# galvanika-board-2_2.net
KiCad netlist of a schematic drawn in EAGLE
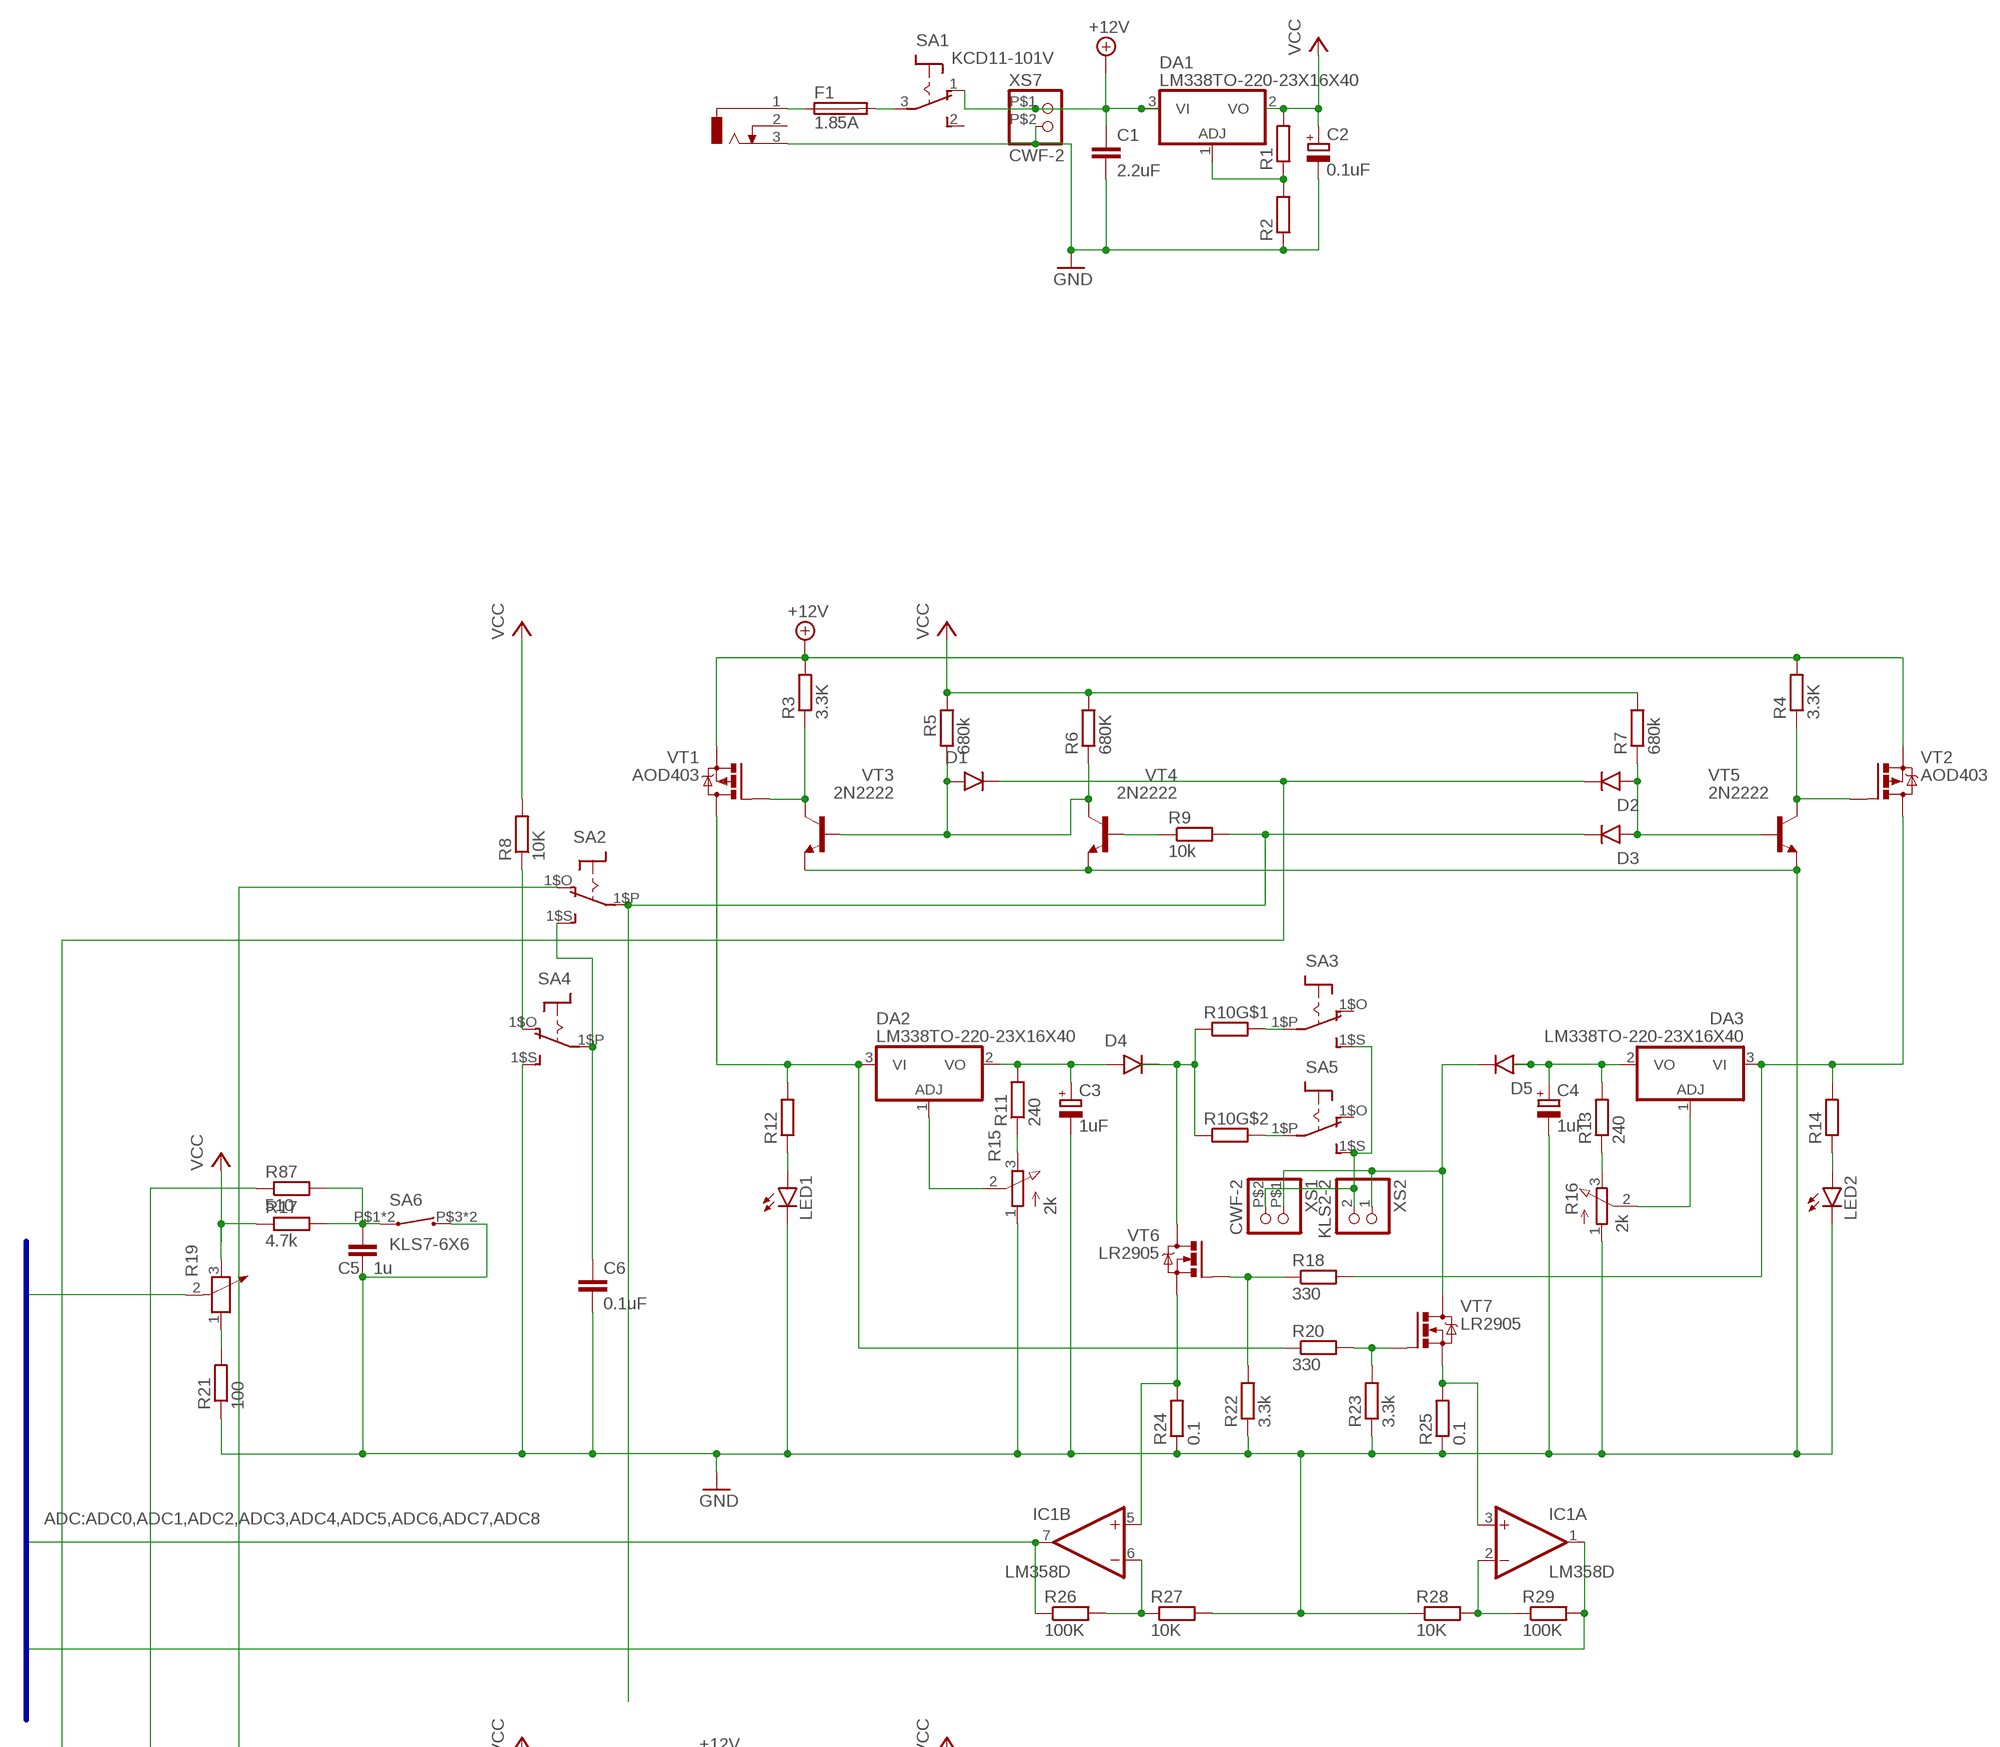
[diagram p0: schematic, sheet 1, part 1 of 2]
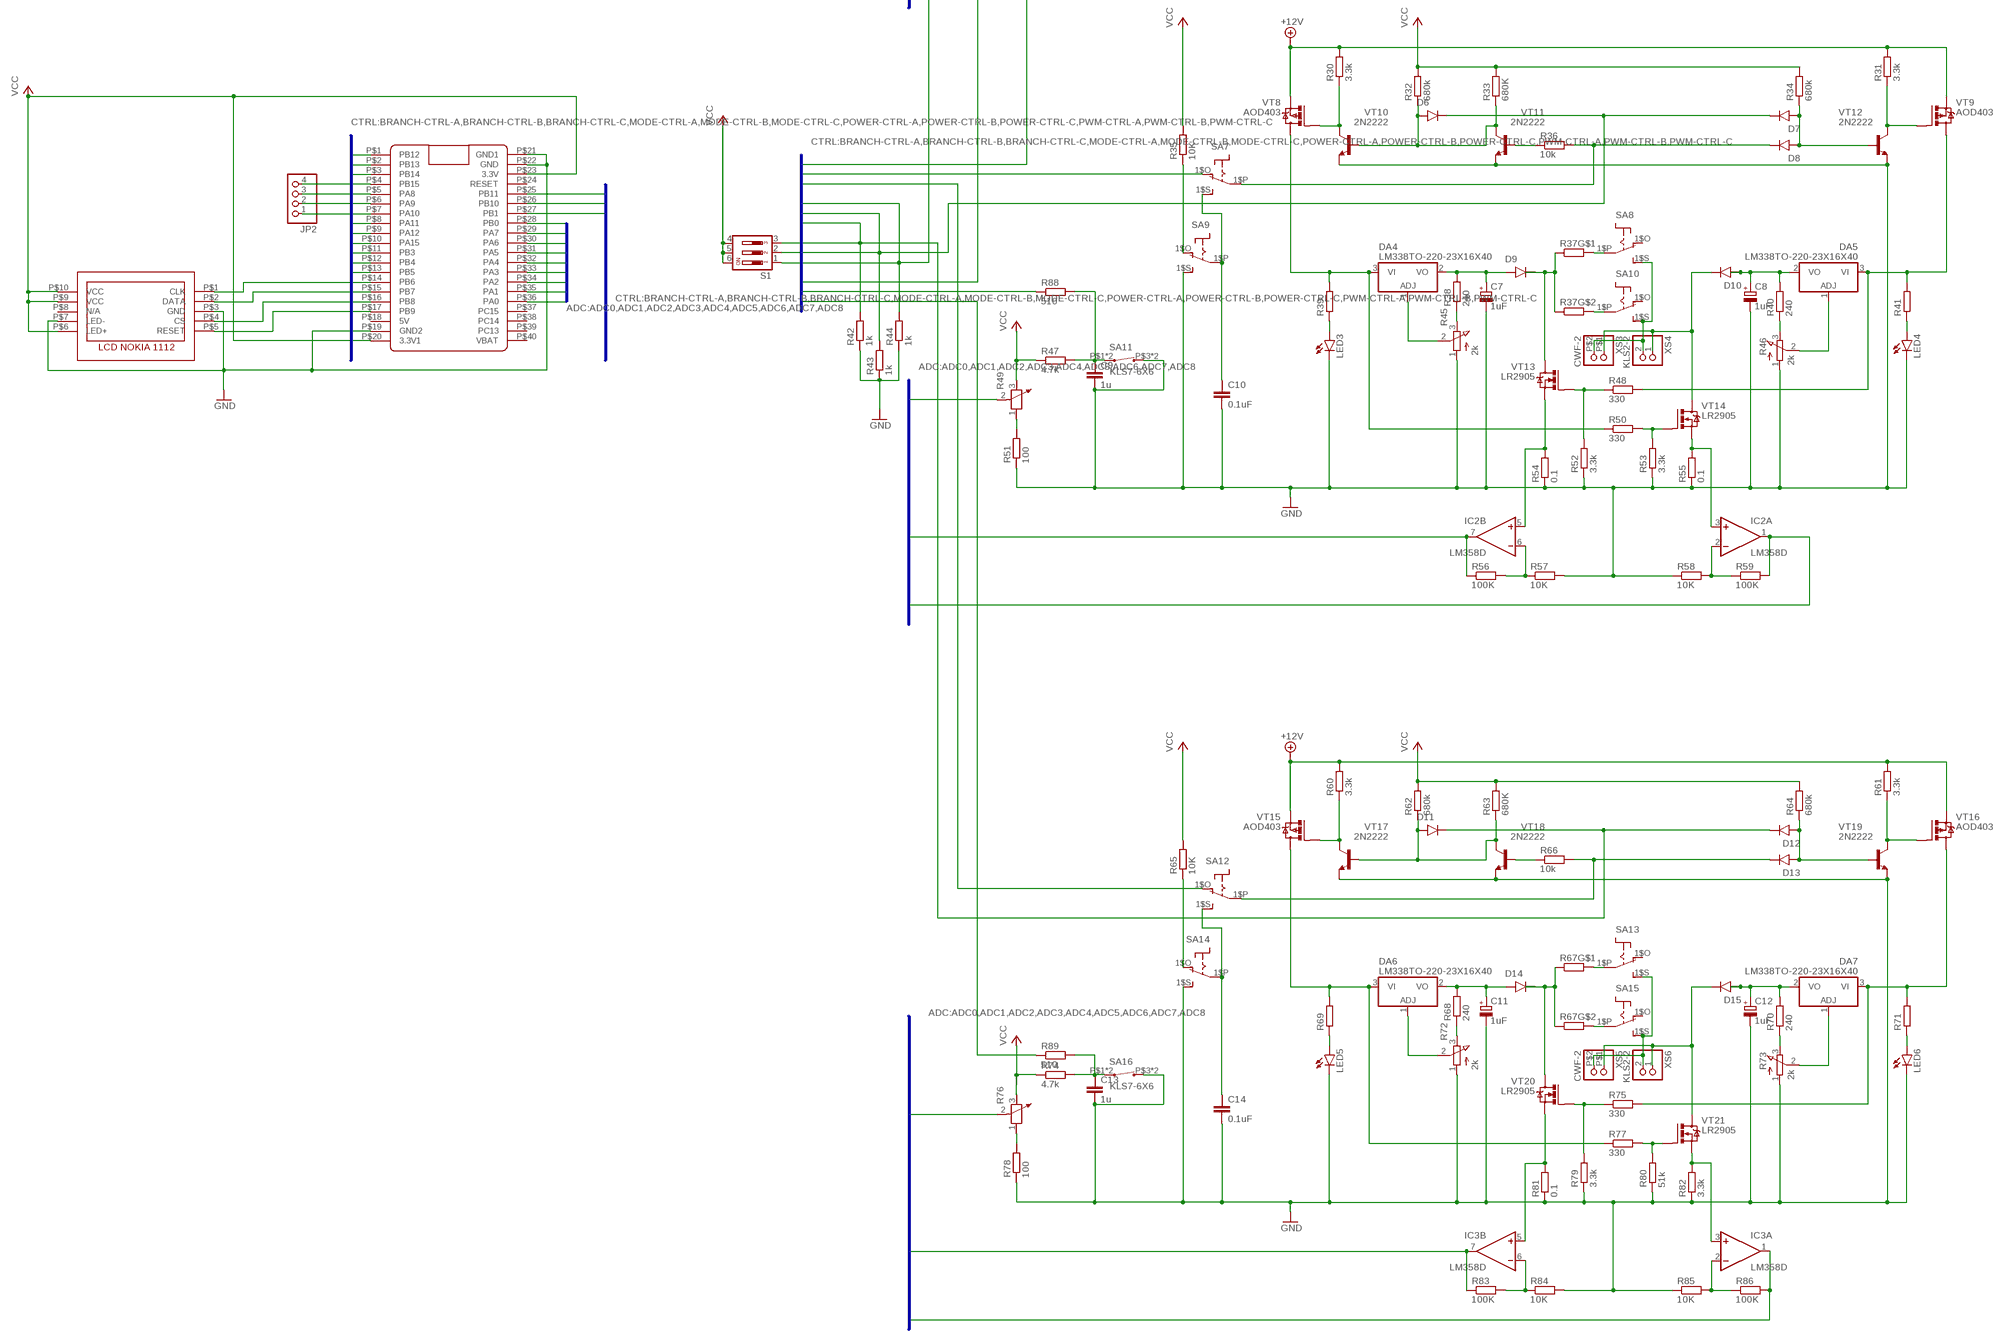
[diagram p1: schematic, sheet 1, part 2 of 2]

(export (version "E")
  (design (tool "Eeschema 10.0.6"))
  (components
    (comp (ref "C1")
      (value "2.2uF")
      (footprint "eagle-import:C025-025X050")
      (libsource (lib "eagle-import") (part "C-EU025-025X050"))
    )
    (comp (ref "C2")
      (value "0.1uF")
      (footprint "eagle-import:E2,5-5")
      (libsource (lib "eagle-import") (part "rcl_334_CPOL-EUE2.5-5"))
    )
    (comp (ref "C3")
      (value "1uF")
      (footprint "eagle-import:E5-4")
      (libsource (lib "eagle-import") (part "CPOL-EUE5-4"))
    )
    (comp (ref "C4")
      (value "1uF")
      (footprint "eagle-import:E5-4")
      (libsource (lib "eagle-import") (part "CPOL-EUE5-4"))
    )
    (comp (ref "C5")
      (value "1u")
      (footprint "eagle-import:C1206")
      (libsource (lib "eagle-import") (part "C-EUC1206"))
    )
    (comp (ref "C6")
      (value "0.1uF")
      (footprint "eagle-import:C1206")
      (libsource (lib "eagle-import") (part "C-EUC1206"))
    )
    (comp (ref "C7")
      (value "1uF")
      (footprint "eagle-import:E5-4")
      (libsource (lib "eagle-import") (part "CPOL-EUE5-4"))
    )
    (comp (ref "C8")
      (value "1uF")
      (footprint "eagle-import:E5-4")
      (libsource (lib "eagle-import") (part "CPOL-EUE5-4"))
    )
    (comp (ref "C9")
      (value "1u")
      (footprint "eagle-import:C1206")
      (libsource (lib "eagle-import") (part "C-EUC1206"))
    )
    (comp (ref "C10")
      (value "0.1uF")
      (footprint "eagle-import:C1206")
      (libsource (lib "eagle-import") (part "C-EUC1206"))
    )
    (comp (ref "C11")
      (value "1uF")
      (footprint "eagle-import:E5-4")
      (libsource (lib "eagle-import") (part "CPOL-EUE5-4"))
    )
    (comp (ref "C12")
      (value "1uF")
      (footprint "eagle-import:E5-4")
      (libsource (lib "eagle-import") (part "CPOL-EUE5-4"))
    )
    (comp (ref "C13")
      (value "1u")
      (footprint "eagle-import:C1206")
      (libsource (lib "eagle-import") (part "C-EUC1206"))
    )
    (comp (ref "C14")
      (value "0.1uF")
      (footprint "eagle-import:C1206")
      (libsource (lib "eagle-import") (part "C-EUC1206"))
    )
    (comp (ref "D1")
      (value "1N4001")
      (footprint "eagle-import:DO41-10")
      (libsource (lib "eagle-import") (part "1N4001"))
    )
    (comp (ref "D2")
      (value "1N4001")
      (footprint "eagle-import:DO41-10")
      (libsource (lib "eagle-import") (part "1N4001"))
    )
    (comp (ref "D3")
      (value "1N4001")
      (footprint "eagle-import:DO41-10")
      (libsource (lib "eagle-import") (part "1N4001"))
    )
    (comp (ref "D4")
      (value "1N4001")
      (footprint "eagle-import:DO41-10")
      (libsource (lib "eagle-import") (part "1N4001"))
    )
    (comp (ref "D5")
      (value "1N4001")
      (footprint "eagle-import:DO41-10")
      (libsource (lib "eagle-import") (part "1N4001"))
    )
    (comp (ref "D6")
      (value "1N4001")
      (footprint "eagle-import:DO41-10")
      (libsource (lib "eagle-import") (part "1N4001"))
    )
    (comp (ref "D7")
      (value "1N4001")
      (footprint "eagle-import:DO41-10")
      (libsource (lib "eagle-import") (part "1N4001"))
    )
    (comp (ref "D8")
      (value "1N4001")
      (footprint "eagle-import:DO41-10")
      (libsource (lib "eagle-import") (part "1N4001"))
    )
    (comp (ref "D9")
      (value "1N4001")
      (footprint "eagle-import:DO41-10")
      (libsource (lib "eagle-import") (part "1N4001"))
    )
    (comp (ref "D10")
      (value "1N4001")
      (footprint "eagle-import:DO41-10")
      (libsource (lib "eagle-import") (part "1N4001"))
    )
    (comp (ref "D11")
      (value "1N4001")
      (footprint "eagle-import:DO41-10")
      (libsource (lib "eagle-import") (part "1N4001"))
    )
    (comp (ref "D12")
      (value "1N4001")
      (footprint "eagle-import:DO41-10")
      (libsource (lib "eagle-import") (part "1N4001"))
    )
    (comp (ref "D13")
      (value "1N4001")
      (footprint "eagle-import:DO41-10")
      (libsource (lib "eagle-import") (part "1N4001"))
    )
    (comp (ref "D14")
      (value "1N4001")
      (footprint "eagle-import:DO41-10")
      (libsource (lib "eagle-import") (part "1N4001"))
    )
    (comp (ref "D15")
      (value "1N4001")
      (footprint "eagle-import:DO41-10")
      (libsource (lib "eagle-import") (part "1N4001"))
    )
    (comp (ref "DA1")
      (value "LM338TO-220-23X16X40")
      (footprint "eagle-import:TO220-23X16X40")
      (libsource (lib "eagle-import") (part "LM338TO-220-23X16X40"))
    )
    (comp (ref "DA2")
      (value "LM338TO-220-23X16X40")
      (footprint "eagle-import:TO220-23X16X40")
      (libsource (lib "eagle-import") (part "LM338TO-220-23X16X40"))
    )
    (comp (ref "DA3")
      (value "LM338TO-220-23X16X40")
      (footprint "eagle-import:TO220-23X16X40")
      (libsource (lib "eagle-import") (part "LM338TO-220-23X16X40"))
    )
    (comp (ref "DA4")
      (value "LM338TO-220-23X16X40")
      (footprint "eagle-import:TO220-23X16X40")
      (libsource (lib "eagle-import") (part "LM338TO-220-23X16X40"))
    )
    (comp (ref "DA5")
      (value "LM338TO-220-23X16X40")
      (footprint "eagle-import:TO220-23X16X40")
      (libsource (lib "eagle-import") (part "LM338TO-220-23X16X40"))
    )
    (comp (ref "DA6")
      (value "LM338TO-220-23X16X40")
      (footprint "eagle-import:TO220-23X16X40")
      (libsource (lib "eagle-import") (part "LM338TO-220-23X16X40"))
    )
    (comp (ref "DA7")
      (value "LM338TO-220-23X16X40")
      (footprint "eagle-import:TO220-23X16X40")
      (libsource (lib "eagle-import") (part "LM338TO-220-23X16X40"))
    )
    (comp (ref "DD1")
      (value "BLUE_PILL")
      (footprint "eagle-import:BLUE_PILL")
      (libsource (lib "eagle-import") (part "BLUE_PILL"))
    )
    (comp (ref "F1")
      (value "1.85A")
      (footprint "eagle-import:MF-R")
      (libsource (lib "eagle-import") (part "MF-R"))
    )
    (comp (ref "HG1")
      (value "WD-G0906WY-BOARD")
      (footprint "eagle-import:WD-G0906WY-BOARD")
      (libsource (lib "eagle-import") (part "WD-G0906WY-BOARD"))
    )
    (comp (ref "IC1")
      (value "LM358D")
      (footprint "eagle-import:SO08")
      (libsource (lib "eagle-import") (part "LM358D"))
    )
    (comp (ref "IC2")
      (value "LM358D")
      (footprint "eagle-import:SO08")
      (libsource (lib "eagle-import") (part "LM358D"))
    )
    (comp (ref "IC3")
      (value "LM358D")
      (footprint "eagle-import:SO08")
      (libsource (lib "eagle-import") (part "LM358D"))
    )
    (comp (ref "J1")
      (value "DCJ0303")
      (footprint "eagle-import:DCJ0303")
      (libsource (lib "eagle-import") (part "DCJ0303"))
    )
    (comp (ref "JP2")
      (value "PINHD-1X4")
      (footprint "eagle-import:1X04")
      (libsource (lib "eagle-import") (part "PINHD-1X4"))
    )
    (comp (ref "LED1")
      (value "LED3MM")
      (footprint "eagle-import:LED3MM")
      (libsource (lib "eagle-import") (part "LED3MM"))
    )
    (comp (ref "LED2")
      (value "LED3MM")
      (footprint "eagle-import:LED3MM")
      (libsource (lib "eagle-import") (part "LED3MM"))
    )
    (comp (ref "LED3")
      (value "LED3MM")
      (footprint "eagle-import:LED3MM")
      (libsource (lib "eagle-import") (part "LED3MM"))
    )
    (comp (ref "LED4")
      (value "LED3MM")
      (footprint "eagle-import:LED3MM")
      (libsource (lib "eagle-import") (part "LED3MM"))
    )
    (comp (ref "LED5")
      (value "LED3MM")
      (footprint "eagle-import:LED3MM")
      (libsource (lib "eagle-import") (part "LED3MM"))
    )
    (comp (ref "LED6")
      (value "LED3MM")
      (footprint "eagle-import:LED3MM")
      (libsource (lib "eagle-import") (part "LED3MM"))
    )
    (comp (ref "R1")
      (value "R-EU_0207/10")
      (footprint "eagle-import:0207_10")
      (libsource (lib "eagle-import") (part "R-EU_0207/10"))
    )
    (comp (ref "R2")
      (value "R-EU_0207/10")
      (footprint "eagle-import:0207_10")
      (libsource (lib "eagle-import") (part "R-EU_0207/10"))
    )
    (comp (ref "R3")
      (value "3.3K")
      (footprint "eagle-import:0207_10")
      (libsource (lib "eagle-import") (part "rcl_334_R-EU_0207/10"))
    )
    (comp (ref "R4")
      (value "3.3K")
      (footprint "eagle-import:0207_10")
      (libsource (lib "eagle-import") (part "rcl_334_R-EU_0207/10"))
    )
    (comp (ref "R5")
      (value "680k")
      (footprint "eagle-import:0207_10")
      (libsource (lib "eagle-import") (part "rcl_334_R-EU_0207/10"))
    )
    (comp (ref "R6")
      (value "680K")
      (footprint "eagle-import:0207_10")
      (libsource (lib "eagle-import") (part "rcl_334_R-EU_0207/10"))
    )
    (comp (ref "R7")
      (value "680k")
      (footprint "eagle-import:0207_10")
      (libsource (lib "eagle-import") (part "rcl_334_R-EU_0207/10"))
    )
    (comp (ref "R8")
      (value "10K")
      (footprint "eagle-import:0207_10")
      (libsource (lib "eagle-import") (part "rcl_334_R-EU_0207/10"))
    )
    (comp (ref "R9")
      (value "10k")
      (footprint "eagle-import:0207_10")
      (libsource (lib "eagle-import") (part "rcl_334_R-EU_0207/10"))
    )
    (comp (ref "R10")
      (value "SQP-5W-2")
      (footprint "eagle-import:SQP-5W-2")
      (libsource (lib "eagle-import") (part "SQP-5W-2"))
    )
    (comp (ref "R11")
      (value "240")
      (footprint "eagle-import:0207_10")
      (libsource (lib "eagle-import") (part "rcl_334_R-EU_0207/10"))
    )
    (comp (ref "R12")
      (value "R-EU_0207/10")
      (footprint "eagle-import:0207_10")
      (libsource (lib "eagle-import") (part "rcl_334_R-EU_0207/10"))
    )
    (comp (ref "R13")
      (value "240")
      (footprint "eagle-import:0207_10")
      (libsource (lib "eagle-import") (part "rcl_334_R-EU_0207/10"))
    )
    (comp (ref "R14")
      (value "R-EU_0207/10")
      (footprint "eagle-import:0207_10")
      (libsource (lib "eagle-import") (part "rcl_334_R-EU_0207/10"))
    )
    (comp (ref "R15")
      (value "2k")
      (footprint "eagle-import:3RP_1610N")
      (libsource (lib "eagle-import") (part "3RP/1610N"))
    )
    (comp (ref "R16")
      (value "2k")
      (footprint "eagle-import:3RP_1610N")
      (libsource (lib "eagle-import") (part "3RP/1610N"))
    )
    (comp (ref "R17")
      (value "4.7k")
      (footprint "eagle-import:R1206")
      (libsource (lib "eagle-import") (part "R-EU_R1206"))
    )
    (comp (ref "R18")
      (value "330")
      (footprint "eagle-import:0207_10")
      (libsource (lib "eagle-import") (part "rcl_334_R-EU_0207/10"))
    )
    (comp (ref "R19")
      (value "R0904N")
      (footprint "eagle-import:R0904N")
      (libsource (lib "eagle-import") (part "R0904N"))
    )
    (comp (ref "R20")
      (value "330")
      (footprint "eagle-import:0207_10")
      (libsource (lib "eagle-import") (part "rcl_334_R-EU_0207/10"))
    )
    (comp (ref "R21")
      (value "100")
      (footprint "eagle-import:R1206")
      (libsource (lib "eagle-import") (part "R-EU_R1206"))
    )
    (comp (ref "R22")
      (value "3.3k")
      (footprint "eagle-import:0207_10")
      (libsource (lib "eagle-import") (part "rcl_334_R-EU_0207/10"))
    )
    (comp (ref "R23")
      (value "3.3k")
      (footprint "eagle-import:0207_10")
      (libsource (lib "eagle-import") (part "rcl_334_R-EU_0207/10"))
    )
    (comp (ref "R24")
      (value "0.1")
      (footprint "eagle-import:0411_12")
      (libsource (lib "eagle-import") (part "rcl_334_R-EU_0411/12"))
    )
    (comp (ref "R25")
      (value "0.1")
      (footprint "eagle-import:0411_12")
      (libsource (lib "eagle-import") (part "rcl_334_R-EU_0411/12"))
    )
    (comp (ref "R26")
      (value "100K")
      (footprint "eagle-import:R1206")
      (libsource (lib "eagle-import") (part "rcl_334_R-EU_R1206"))
    )
    (comp (ref "R27")
      (value "10K")
      (footprint "eagle-import:R1206")
      (libsource (lib "eagle-import") (part "rcl_334_R-EU_R1206"))
    )
    (comp (ref "R28")
      (value "10K")
      (footprint "eagle-import:R1206")
      (libsource (lib "eagle-import") (part "rcl_334_R-EU_R1206"))
    )
    (comp (ref "R29")
      (value "100K")
      (footprint "eagle-import:R1206")
      (libsource (lib "eagle-import") (part "rcl_334_R-EU_R1206"))
    )
    (comp (ref "R30")
      (value "3.3k")
      (footprint "eagle-import:0207_10")
      (libsource (lib "eagle-import") (part "rcl_334_R-EU_0207/10"))
    )
    (comp (ref "R31")
      (value "3.3k")
      (footprint "eagle-import:0207_10")
      (libsource (lib "eagle-import") (part "rcl_334_R-EU_0207/10"))
    )
    (comp (ref "R32")
      (value "680k")
      (footprint "eagle-import:0207_10")
      (libsource (lib "eagle-import") (part "rcl_334_R-EU_0207/10"))
    )
    (comp (ref "R33")
      (value "680K")
      (footprint "eagle-import:0207_10")
      (libsource (lib "eagle-import") (part "rcl_334_R-EU_0207/10"))
    )
    (comp (ref "R34")
      (value "680k")
      (footprint "eagle-import:0207_10")
      (libsource (lib "eagle-import") (part "rcl_334_R-EU_0207/10"))
    )
    (comp (ref "R35")
      (value "10K")
      (footprint "eagle-import:0207_10")
      (libsource (lib "eagle-import") (part "rcl_334_R-EU_0207/10"))
    )
    (comp (ref "R36")
      (value "10k")
      (footprint "eagle-import:0207_10")
      (libsource (lib "eagle-import") (part "rcl_334_R-EU_0207/10"))
    )
    (comp (ref "R37")
      (value "SQP-5W-2")
      (footprint "eagle-import:SQP-5W-2")
      (libsource (lib "eagle-import") (part "SQP-5W-2"))
    )
    (comp (ref "R38")
      (value "240")
      (footprint "eagle-import:0207_10")
      (libsource (lib "eagle-import") (part "R-EU_0207/10"))
    )
    (comp (ref "R39")
      (value "R-EU_0207/10")
      (footprint "eagle-import:0207_10")
      (libsource (lib "eagle-import") (part "R-EU_0207/10"))
    )
    (comp (ref "R40")
      (value "240")
      (footprint "eagle-import:0207_10")
      (libsource (lib "eagle-import") (part "rcl_334_R-EU_0207/10"))
    )
    (comp (ref "R41")
      (value "R-EU_0207/10")
      (footprint "eagle-import:0207_10")
      (libsource (lib "eagle-import") (part "R-EU_0207/10"))
    )
    (comp (ref "R42")
      (value "1k")
      (footprint "eagle-import:R1206")
      (libsource (lib "eagle-import") (part "R-EU_R1206"))
    )
    (comp (ref "R43")
      (value "1k")
      (footprint "eagle-import:R1206")
      (libsource (lib "eagle-import") (part "R-EU_R1206"))
    )
    (comp (ref "R44")
      (value "1k")
      (footprint "eagle-import:R1206")
      (libsource (lib "eagle-import") (part "R-EU_R1206"))
    )
    (comp (ref "R45")
      (value "2k")
      (footprint "eagle-import:3RP_1610N")
      (libsource (lib "eagle-import") (part "3RP/1610N"))
    )
    (comp (ref "R46")
      (value "2k")
      (footprint "eagle-import:3RP_1610N")
      (libsource (lib "eagle-import") (part "3RP/1610N"))
    )
    (comp (ref "R47")
      (value "4.7k")
      (footprint "eagle-import:R1206")
      (libsource (lib "eagle-import") (part "R-EU_R1206"))
    )
    (comp (ref "R48")
      (value "330")
      (footprint "eagle-import:0207_10")
      (libsource (lib "eagle-import") (part "rcl_334_R-EU_0207/10"))
    )
    (comp (ref "R49")
      (value "R0904N")
      (footprint "eagle-import:R0904N")
      (libsource (lib "eagle-import") (part "R0904N"))
    )
    (comp (ref "R50")
      (value "330")
      (footprint "eagle-import:0207_10")
      (libsource (lib "eagle-import") (part "rcl_334_R-EU_0207/10"))
    )
    (comp (ref "R51")
      (value "100")
      (footprint "eagle-import:R1206")
      (libsource (lib "eagle-import") (part "R-EU_R1206"))
    )
    (comp (ref "R52")
      (value "3.3k")
      (footprint "eagle-import:0207_10")
      (libsource (lib "eagle-import") (part "rcl_334_R-EU_0207/10"))
    )
    (comp (ref "R53")
      (value "3.3k")
      (footprint "eagle-import:0207_10")
      (libsource (lib "eagle-import") (part "rcl_334_R-EU_0207/10"))
    )
    (comp (ref "R54")
      (value "0.1")
      (footprint "eagle-import:0411_12")
      (libsource (lib "eagle-import") (part "rcl_334_R-EU_0411/12"))
    )
    (comp (ref "R55")
      (value "0.1")
      (footprint "eagle-import:0411_12")
      (libsource (lib "eagle-import") (part "rcl_334_R-EU_0411/12"))
    )
    (comp (ref "R56")
      (value "100K")
      (footprint "eagle-import:R1206")
      (libsource (lib "eagle-import") (part "rcl_334_R-EU_R1206"))
    )
    (comp (ref "R57")
      (value "10K")
      (footprint "eagle-import:R1206")
      (libsource (lib "eagle-import") (part "rcl_334_R-EU_R1206"))
    )
    (comp (ref "R58")
      (value "10K")
      (footprint "eagle-import:R1206")
      (libsource (lib "eagle-import") (part "rcl_334_R-EU_R1206"))
    )
    (comp (ref "R59")
      (value "100K")
      (footprint "eagle-import:R1206")
      (libsource (lib "eagle-import") (part "rcl_334_R-EU_R1206"))
    )
    (comp (ref "R60")
      (value "3.3k")
      (footprint "eagle-import:0207_10")
      (libsource (lib "eagle-import") (part "rcl_334_R-EU_0207/10"))
    )
    (comp (ref "R61")
      (value "3.3k")
      (footprint "eagle-import:0207_10")
      (libsource (lib "eagle-import") (part "rcl_334_R-EU_0207/10"))
    )
    (comp (ref "R62")
      (value "680k")
      (footprint "eagle-import:0207_10")
      (libsource (lib "eagle-import") (part "rcl_334_R-EU_0207/10"))
    )
    (comp (ref "R63")
      (value "680K")
      (footprint "eagle-import:0207_10")
      (libsource (lib "eagle-import") (part "rcl_334_R-EU_0207/10"))
    )
    (comp (ref "R64")
      (value "680k")
      (footprint "eagle-import:0207_10")
      (libsource (lib "eagle-import") (part "rcl_334_R-EU_0207/10"))
    )
    (comp (ref "R65")
      (value "10K")
      (footprint "eagle-import:0207_10")
      (libsource (lib "eagle-import") (part "rcl_334_R-EU_0207/10"))
    )
    (comp (ref "R66")
      (value "10k")
      (footprint "eagle-import:0207_10")
      (libsource (lib "eagle-import") (part "rcl_334_R-EU_0207/10"))
    )
    (comp (ref "R67")
      (value "SQP-5W-2")
      (footprint "eagle-import:SQP-5W-2")
      (libsource (lib "eagle-import") (part "SQP-5W-2"))
    )
    (comp (ref "R68")
      (value "240")
      (footprint "eagle-import:0207_10")
      (libsource (lib "eagle-import") (part "rcl_334_R-EU_0207/10"))
    )
    (comp (ref "R69")
      (value "R-EU_0207/10")
      (footprint "eagle-import:0207_10")
      (libsource (lib "eagle-import") (part "rcl_334_R-EU_0207/10"))
    )
    (comp (ref "R70")
      (value "240")
      (footprint "eagle-import:0207_10")
      (libsource (lib "eagle-import") (part "rcl_334_R-EU_0207/10"))
    )
    (comp (ref "R71")
      (value "R-EU_0207/10")
      (footprint "eagle-import:0207_10")
      (libsource (lib "eagle-import") (part "rcl_334_R-EU_0207/10"))
    )
    (comp (ref "R72")
      (value "2k")
      (footprint "eagle-import:3RP_1610N")
      (libsource (lib "eagle-import") (part "3RP/1610N"))
    )
    (comp (ref "R73")
      (value "2k")
      (footprint "eagle-import:3RP_1610N")
      (libsource (lib "eagle-import") (part "3RP/1610N"))
    )
    (comp (ref "R74")
      (value "4.7k")
      (footprint "eagle-import:R1206")
      (libsource (lib "eagle-import") (part "R-EU_R1206"))
    )
    (comp (ref "R75")
      (value "330")
      (footprint "eagle-import:0207_10")
      (libsource (lib "eagle-import") (part "rcl_334_R-EU_0207/10"))
    )
    (comp (ref "R76")
      (value "R0904N")
      (footprint "eagle-import:R0904N")
      (libsource (lib "eagle-import") (part "R0904N"))
    )
    (comp (ref "R77")
      (value "330")
      (footprint "eagle-import:0207_10")
      (libsource (lib "eagle-import") (part "rcl_334_R-EU_0207/10"))
    )
    (comp (ref "R78")
      (value "100")
      (footprint "eagle-import:R1206")
      (libsource (lib "eagle-import") (part "R-EU_R1206"))
    )
    (comp (ref "R79")
      (value "3.3k")
      (footprint "eagle-import:0207_10")
      (libsource (lib "eagle-import") (part "rcl_334_R-EU_0207/10"))
    )
    (comp (ref "R80")
      (value "51k")
      (footprint "eagle-import:0207_10")
      (libsource (lib "eagle-import") (part "rcl_334_R-EU_0207/10"))
    )
    (comp (ref "R81")
      (value "0.1")
      (footprint "eagle-import:0411_12")
      (libsource (lib "eagle-import") (part "rcl_334_R-EU_0411/12"))
    )
    (comp (ref "R82")
      (value "3.3k")
      (footprint "eagle-import:0411_12")
      (libsource (lib "eagle-import") (part "rcl_334_R-EU_0411/12"))
    )
    (comp (ref "R83")
      (value "100K")
      (footprint "eagle-import:R1206")
      (libsource (lib "eagle-import") (part "rcl_334_R-EU_R1206"))
    )
    (comp (ref "R84")
      (value "10K")
      (footprint "eagle-import:R1206")
      (libsource (lib "eagle-import") (part "rcl_334_R-EU_R1206"))
    )
    (comp (ref "R85")
      (value "10K")
      (footprint "eagle-import:R1206")
      (libsource (lib "eagle-import") (part "rcl_334_R-EU_R1206"))
    )
    (comp (ref "R86")
      (value "100K")
      (footprint "eagle-import:R1206")
      (libsource (lib "eagle-import") (part "rcl_334_R-EU_R1206"))
    )
    (comp (ref "R87")
      (value "510")
      (footprint "eagle-import:R1206")
      (libsource (lib "eagle-import") (part "R-EU_R1206"))
    )
    (comp (ref "R88")
      (value "510")
      (footprint "eagle-import:R1206")
      (libsource (lib "eagle-import") (part "R-EU_R1206"))
    )
    (comp (ref "R89")
      (value "510")
      (footprint "eagle-import:R1206")
      (libsource (lib "eagle-import") (part "R-EU_R1206"))
    )
    (comp (ref "S1")
      (value "DS03")
      (footprint "eagle-import:DS-03")
      (libsource (lib "eagle-import") (part "DS03"))
    )
    (comp (ref "SA1")
      (value "KCD11-101V")
      (footprint "eagle-import:KCD11-101-V")
      (libsource (lib "eagle-import") (part "KCD11-101V"))
    )
    (comp (ref "SA2")
      (value "SS12D00DIP")
      (footprint "eagle-import:SS12D00")
      (libsource (lib "eagle-import") (part "SS12D00DIP"))
    )
    (comp (ref "SA3")
      (value "SS12D00DIP")
      (footprint "eagle-import:SS12D00")
      (libsource (lib "eagle-import") (part "SS12D00DIP"))
    )
    (comp (ref "SA4")
      (value "SS12D00DIP")
      (footprint "eagle-import:SS12D00")
      (libsource (lib "eagle-import") (part "SS12D00DIP"))
    )
    (comp (ref "SA5")
      (value "SS12D00DIP")
      (footprint "eagle-import:SS12D00")
      (libsource (lib "eagle-import") (part "SS12D00DIP"))
    )
    (comp (ref "SA6")
      (value "KLS7-6X6")
      (footprint "eagle-import:KLS7-6X6")
      (libsource (lib "eagle-import") (part "KLS7-6X6"))
    )
    (comp (ref "SA7")
      (value "SS12D00DIP")
      (footprint "eagle-import:SS12D00")
      (libsource (lib "eagle-import") (part "SS12D00DIP"))
    )
    (comp (ref "SA8")
      (value "SS12D00DIP")
      (footprint "eagle-import:SS12D00")
      (libsource (lib "eagle-import") (part "SS12D00DIP"))
    )
    (comp (ref "SA9")
      (value "SS12D00DIP")
      (footprint "eagle-import:SS12D00")
      (libsource (lib "eagle-import") (part "SS12D00DIP"))
    )
    (comp (ref "SA10")
      (value "SS12D00DIP")
      (footprint "eagle-import:SS12D00")
      (libsource (lib "eagle-import") (part "SS12D00DIP"))
    )
    (comp (ref "SA11")
      (value "KLS7-6X6")
      (footprint "eagle-import:KLS7-6X6")
      (libsource (lib "eagle-import") (part "KLS7-6X6"))
    )
    (comp (ref "SA12")
      (value "SS12D00DIP")
      (footprint "eagle-import:SS12D00")
      (libsource (lib "eagle-import") (part "SS12D00DIP"))
    )
    (comp (ref "SA13")
      (value "SS12D00DIP")
      (footprint "eagle-import:SS12D00")
      (libsource (lib "eagle-import") (part "SS12D00DIP"))
    )
    (comp (ref "SA14")
      (value "SS12D00DIP")
      (footprint "eagle-import:SS12D00")
      (libsource (lib "eagle-import") (part "SS12D00DIP"))
    )
    (comp (ref "SA15")
      (value "SS12D00DIP")
      (footprint "eagle-import:SS12D00")
      (libsource (lib "eagle-import") (part "SS12D00DIP"))
    )
    (comp (ref "SA16")
      (value "KLS7-6X6")
      (footprint "eagle-import:KLS7-6X6")
      (libsource (lib "eagle-import") (part "KLS7-6X6"))
    )
    (comp (ref "VT1")
      (value "AOD403")
      (footprint "eagle-import:TO252")
      (libsource (lib "eagle-import") (part "AOD403"))
    )
    (comp (ref "VT2")
      (value "AOD403")
      (footprint "eagle-import:TO252")
      (libsource (lib "eagle-import") (part "AOD403"))
    )
    (comp (ref "VT3")
      (value "2N2222")
      (footprint "eagle-import:TO92")
      (libsource (lib "eagle-import") (part "2N2222"))
    )
    (comp (ref "VT4")
      (value "2N2222")
      (footprint "eagle-import:TO92")
      (libsource (lib "eagle-import") (part "2N2222"))
    )
    (comp (ref "VT5")
      (value "2N2222")
      (footprint "eagle-import:TO92")
      (libsource (lib "eagle-import") (part "2N2222"))
    )
    (comp (ref "VT6")
      (value "LR2905")
      (footprint "eagle-import:TO252")
      (libsource (lib "eagle-import") (part "LR2905"))
    )
    (comp (ref "VT7")
      (value "LR2905")
      (footprint "eagle-import:TO252")
      (libsource (lib "eagle-import") (part "LR2905"))
    )
    (comp (ref "VT8")
      (value "AOD403")
      (footprint "eagle-import:TO252")
      (libsource (lib "eagle-import") (part "AOD403"))
    )
    (comp (ref "VT9")
      (value "AOD403")
      (footprint "eagle-import:TO252")
      (libsource (lib "eagle-import") (part "AOD403"))
    )
    (comp (ref "VT10")
      (value "2N2222")
      (footprint "eagle-import:TO92")
      (libsource (lib "eagle-import") (part "2N2222"))
    )
    (comp (ref "VT11")
      (value "2N2222")
      (footprint "eagle-import:TO92")
      (libsource (lib "eagle-import") (part "2N2222"))
    )
    (comp (ref "VT12")
      (value "2N2222")
      (footprint "eagle-import:TO92")
      (libsource (lib "eagle-import") (part "2N2222"))
    )
    (comp (ref "VT13")
      (value "LR2905")
      (footprint "eagle-import:TO252")
      (libsource (lib "eagle-import") (part "LR2905"))
    )
    (comp (ref "VT14")
      (value "LR2905")
      (footprint "eagle-import:TO252")
      (libsource (lib "eagle-import") (part "LR2905"))
    )
    (comp (ref "VT15")
      (value "AOD403")
      (footprint "eagle-import:TO252")
      (libsource (lib "eagle-import") (part "AOD403"))
    )
    (comp (ref "VT16")
      (value "AOD403")
      (footprint "eagle-import:TO252")
      (libsource (lib "eagle-import") (part "AOD403"))
    )
    (comp (ref "VT17")
      (value "2N2222")
      (footprint "eagle-import:TO92")
      (libsource (lib "eagle-import") (part "2N2222"))
    )
    (comp (ref "VT18")
      (value "2N2222")
      (footprint "eagle-import:TO92")
      (libsource (lib "eagle-import") (part "2N2222"))
    )
    (comp (ref "VT19")
      (value "2N2222")
      (footprint "eagle-import:TO92")
      (libsource (lib "eagle-import") (part "2N2222"))
    )
    (comp (ref "VT20")
      (value "LR2905")
      (footprint "eagle-import:TO252")
      (libsource (lib "eagle-import") (part "LR2905"))
    )
    (comp (ref "VT21")
      (value "LR2905")
      (footprint "eagle-import:TO252")
      (libsource (lib "eagle-import") (part "LR2905"))
    )
    (comp (ref "XS1")
      (value "CWF-2")
      (footprint "eagle-import:CWF-2")
      (libsource (lib "eagle-import") (part "CWF-2"))
    )
    (comp (ref "XS2")
      (value "KLS2-2")
      (footprint "eagle-import:KLS2-2")
      (libsource (lib "eagle-import") (part "KLS2-2"))
    )
    (comp (ref "XS3")
      (value "CWF-2")
      (footprint "eagle-import:CWF-2")
      (libsource (lib "eagle-import") (part "CWF-2"))
    )
    (comp (ref "XS4")
      (value "KLS2-2")
      (footprint "eagle-import:KLS2-2")
      (libsource (lib "eagle-import") (part "KLS2-2"))
    )
    (comp (ref "XS5")
      (value "CWF-2")
      (footprint "eagle-import:CWF-2")
      (libsource (lib "eagle-import") (part "CWF-2"))
    )
    (comp (ref "XS6")
      (value "KLS2-2")
      (footprint "eagle-import:KLS2-2")
      (libsource (lib "eagle-import") (part "KLS2-2"))
    )
    (comp (ref "XS7")
      (value "CWF-2")
      (footprint "eagle-import:CWF-2")
      (libsource (lib "eagle-import") (part "CWF-2"))
    )
  )
  (nets
    (net (code "3") (name "+12V") (class "Default")
      (node (ref "C1") (pin "1") (pinfunction "1_1") (pintype "passive"))
      (node (ref "DA1") (pin "3") (pinfunction "VI_3") (pintype "input"))
      (node (ref "R3") (pin "2") (pinfunction "2_2") (pintype "passive"))
      (node (ref "R30") (pin "2") (pinfunction "2_2") (pintype "passive"))
      (node (ref "R31") (pin "2") (pinfunction "2_2") (pintype "passive"))
      (node (ref "R4") (pin "2") (pinfunction "2_2") (pintype "passive"))
      (node (ref "R60") (pin "2") (pinfunction "2_2") (pintype "passive"))
      (node (ref "R61") (pin "2") (pinfunction "2_2") (pintype "passive"))
      (node (ref "SA1") (pin "1") (pinfunction "O_1") (pintype "passive"))
      (node (ref "VT1") (pin "2") (pinfunction "S_2") (pintype "passive"))
      (node (ref "VT15") (pin "2") (pinfunction "S_2") (pintype "passive"))
      (node (ref "VT16") (pin "2") (pinfunction "S_2") (pintype "passive"))
      (node (ref "VT2") (pin "2") (pinfunction "S_2") (pintype "passive"))
      (node (ref "VT8") (pin "2") (pinfunction "S_2") (pintype "passive"))
      (node (ref "VT9") (pin "2") (pinfunction "S_2") (pintype "passive"))
      (node (ref "XS7") (pin "P$1") (pinfunction "1_P$1") (pintype "passive"))
    )
    (net (code "4") (name "/ADC0") (class "Default")
      (node (ref "DD1") (pin "P$36") (pinfunction "PA0_P$36") (pintype "bidirectional"))
      (node (ref "R19") (pin "2") (pinfunction "3_2") (pintype "passive"))
    )
    (net (code "5") (name "/ADC1") (class "Default")
      (node (ref "DD1") (pin "P$35") (pinfunction "PA1_P$35") (pintype "bidirectional"))
      (node (ref "R49") (pin "2") (pinfunction "3_2") (pintype "passive"))
    )
    (net (code "6") (name "/ADC2") (class "Default")
      (node (ref "DD1") (pin "P$34") (pinfunction "PA2_P$34") (pintype "bidirectional"))
      (node (ref "IC1") (pin "7") (pinfunction "OUT_7") (pintype "output"))
      (node (ref "R26") (pin "1") (pinfunction "1_1") (pintype "passive"))
    )
    (net (code "7") (name "/ADC3") (class "Default")
      (node (ref "DD1") (pin "P$33") (pinfunction "PA3_P$33") (pintype "bidirectional"))
      (node (ref "IC1") (pin "1") (pinfunction "OUT_1") (pintype "output"))
      (node (ref "R29") (pin "2") (pinfunction "2_2") (pintype "passive"))
    )
    (net (code "8") (name "/ADC4") (class "Default")
      (node (ref "DD1") (pin "P$32") (pinfunction "PA4_P$32") (pintype "bidirectional"))
      (node (ref "R76") (pin "2") (pinfunction "3_2") (pintype "passive"))
    )
    (net (code "9") (name "/ADC5") (class "Default")
      (node (ref "DD1") (pin "P$31") (pinfunction "PA5_P$31") (pintype "bidirectional"))
      (node (ref "IC2") (pin "1") (pinfunction "OUT_1") (pintype "output"))
      (node (ref "R59") (pin "2") (pinfunction "2_2") (pintype "passive"))
    )
    (net (code "10") (name "/ADC6") (class "Default")
      (node (ref "DD1") (pin "P$30") (pinfunction "PA6_P$30") (pintype "bidirectional"))
      (node (ref "IC2") (pin "7") (pinfunction "OUT_7") (pintype "output"))
      (node (ref "R56") (pin "1") (pinfunction "1_1") (pintype "passive"))
    )
    (net (code "11") (name "/ADC7") (class "Default")
      (node (ref "DD1") (pin "P$29") (pinfunction "PA7_P$29") (pintype "bidirectional"))
      (node (ref "IC3") (pin "7") (pinfunction "OUT_7") (pintype "output"))
      (node (ref "R83") (pin "1") (pinfunction "1_1") (pintype "passive"))
    )
    (net (code "12") (name "/ADC8") (class "Default")
      (node (ref "DD1") (pin "P$28") (pinfunction "PB0_P$28") (pintype "bidirectional"))
      (node (ref "IC3") (pin "1") (pinfunction "OUT_1") (pintype "output"))
      (node (ref "R86") (pin "2") (pinfunction "2_2") (pintype "passive"))
    )
    (net (code "13") (name "/BRANCH-CTRL-A") (class "Default")
      (node (ref "D3") (pin "C") (pinfunction "CATHODE_C") (pintype "passive"))
      (node (ref "DD1") (pin "P$10") (pinfunction "PA15_P$10") (pintype "bidirectional"))
      (node (ref "R9") (pin "2") (pinfunction "2_2") (pintype "passive"))
      (node (ref "SA2") (pin "1$P") (pinfunction "P_1$P") (pintype "passive"))
    )
    (net (code "14") (name "/BRANCH-CTRL-B") (class "Default")
      (node (ref "D8") (pin "C") (pinfunction "CATHODE_C") (pintype "passive"))
      (node (ref "DD1") (pin "P$9") (pinfunction "PA12_P$9") (pintype "bidirectional"))
      (node (ref "R36") (pin "2") (pinfunction "2_2") (pintype "passive"))
      (node (ref "SA7") (pin "1$P") (pinfunction "P_1$P") (pintype "passive"))
    )
    (net (code "15") (name "/BRANCH-CTRL-C") (class "Default")
      (node (ref "D13") (pin "C") (pinfunction "CATHODE_C") (pintype "passive"))
      (node (ref "DD1") (pin "P$8") (pinfunction "PA11_P$8") (pintype "bidirectional"))
      (node (ref "R66") (pin "2") (pinfunction "2_2") (pintype "passive"))
      (node (ref "SA12") (pin "1$P") (pinfunction "P_1$P") (pintype "passive"))
    )
    (net (code "16") (name "/MODE-CTRL-A") (class "Default")
      (node (ref "DD1") (pin "P$13") (pinfunction "PB5_P$13") (pintype "bidirectional"))
      (node (ref "R87") (pin "1") (pinfunction "1_1") (pintype "passive"))
    )
    (net (code "17") (name "/MODE-CTRL-B") (class "Default")
      (node (ref "DD1") (pin "P$12") (pinfunction "PB4_P$12") (pintype "bidirectional"))
      (node (ref "R88") (pin "1") (pinfunction "1_1") (pintype "passive"))
    )
    (net (code "18") (name "/MODE-CTRL-C") (class "Default")
      (node (ref "DD1") (pin "P$11") (pinfunction "PB3_P$11") (pintype "bidirectional"))
      (node (ref "R89") (pin "1") (pinfunction "1_1") (pintype "passive"))
    )
    (net (code "19") (name "/POWER-CTRL-A") (class "Default")
      (node (ref "D1") (pin "C") (pinfunction "CATHODE_C") (pintype "passive"))
      (node (ref "D2") (pin "C") (pinfunction "CATHODE_C") (pintype "passive"))
      (node (ref "DD1") (pin "P$27") (pinfunction "PB1_P$27") (pintype "bidirectional"))
      (node (ref "R44") (pin "2") (pinfunction "2_2") (pintype "passive"))
      (node (ref "S1") (pin "1") (pinfunction "1_1") (pintype "passive"))
    )
    (net (code "20") (name "/POWER-CTRL-B") (class "Default")
      (node (ref "D6") (pin "C") (pinfunction "CATHODE_C") (pintype "passive"))
      (node (ref "D7") (pin "C") (pinfunction "CATHODE_C") (pintype "passive"))
      (node (ref "DD1") (pin "P$26") (pinfunction "PB10_P$26") (pintype "bidirectional"))
      (node (ref "R43") (pin "2") (pinfunction "2_2") (pintype "passive"))
      (node (ref "S1") (pin "2") (pinfunction "2_2") (pintype "passive"))
    )
    (net (code "21") (name "/POWER-CTRL-C") (class "Default")
      (node (ref "D11") (pin "C") (pinfunction "CATHODE_C") (pintype "passive"))
      (node (ref "D12") (pin "C") (pinfunction "CATHODE_C") (pintype "passive"))
      (node (ref "DD1") (pin "P$25") (pinfunction "PB11_P$25") (pintype "bidirectional"))
      (node (ref "R42") (pin "2") (pinfunction "2_2") (pintype "passive"))
      (node (ref "S1") (pin "3") (pinfunction "3_3") (pintype "passive"))
    )
    (net (code "22") (name "/PWM-CTRL-A") (class "Default")
      (node (ref "DD1") (pin "P$2") (pinfunction "PB13_P$2") (pintype "bidirectional"))
      (node (ref "SA2") (pin "1$O") (pinfunction "O_1$O") (pintype "passive"))
    )
    (net (code "23") (name "/PWM-CTRL-B") (class "Default")
      (node (ref "DD1") (pin "P$3") (pinfunction "PB14_P$3") (pintype "bidirectional"))
      (node (ref "SA7") (pin "1$O") (pinfunction "O_1$O") (pintype "passive"))
    )
    (net (code "24") (name "/PWM-CTRL-C") (class "Default")
      (node (ref "DD1") (pin "P$1") (pinfunction "PB12_P$1") (pintype "bidirectional"))
      (node (ref "SA12") (pin "1$O") (pinfunction "O_1$O") (pintype "passive"))
    )
    (net (code "27") (name "GND") (class "Default")
      (node (ref "C1") (pin "2") (pinfunction "2_2") (pintype "passive"))
      (node (ref "C10") (pin "2") (pinfunction "2_2") (pintype "passive"))
      (node (ref "C11") (pin "-") (pinfunction "-_-") (pintype "passive"))
      (node (ref "C12") (pin "-") (pinfunction "-_-") (pintype "passive"))
      (node (ref "C13") (pin "2") (pinfunction "2_2") (pintype "passive"))
      (node (ref "C14") (pin "2") (pinfunction "2_2") (pintype "passive"))
      (node (ref "C2") (pin "-") (pinfunction "-_-") (pintype "passive"))
      (node (ref "C3") (pin "-") (pinfunction "-_-") (pintype "passive"))
      (node (ref "C4") (pin "-") (pinfunction "-_-") (pintype "passive"))
      (node (ref "C5") (pin "2") (pinfunction "2_2") (pintype "passive"))
      (node (ref "C6") (pin "2") (pinfunction "2_2") (pintype "passive"))
      (node (ref "C7") (pin "-") (pinfunction "-_-") (pintype "passive"))
      (node (ref "C8") (pin "-") (pinfunction "-_-") (pintype "passive"))
      (node (ref "C9") (pin "2") (pinfunction "2_2") (pintype "passive"))
      (node (ref "DD1") (pin "P$19") (pinfunction "GND2_P$19") (pintype "bidirectional"))
      (node (ref "DD1") (pin "P$21") (pinfunction "GND1_P$21") (pintype "power_in"))
      (node (ref "DD1") (pin "P$22") (pinfunction "GND_P$22") (pintype "bidirectional"))
      (node (ref "HG1") (pin "P$3") (pinfunction "GND_P$3") (pintype "bidirectional"))
      (node (ref "HG1") (pin "P$7") (pinfunction "LED-_P$7") (pintype "bidirectional"))
      (node (ref "J1") (pin "3") (pinfunction "3_3") (pintype "passive"))
      (node (ref "LED1") (pin "K") (pinfunction "C_K") (pintype "passive"))
      (node (ref "LED2") (pin "K") (pinfunction "C_K") (pintype "passive"))
      (node (ref "LED3") (pin "K") (pinfunction "C_K") (pintype "passive"))
      (node (ref "LED4") (pin "K") (pinfunction "C_K") (pintype "passive"))
      (node (ref "LED5") (pin "K") (pinfunction "C_K") (pintype "passive"))
      (node (ref "LED6") (pin "K") (pinfunction "C_K") (pintype "passive"))
      (node (ref "R15") (pin "1") (pinfunction "A_1") (pintype "passive"))
      (node (ref "R16") (pin "1") (pinfunction "A_1") (pintype "passive"))
      (node (ref "R2") (pin "1") (pinfunction "1_1") (pintype "passive"))
      (node (ref "R21") (pin "1") (pinfunction "1_1") (pintype "passive"))
      (node (ref "R22") (pin "1") (pinfunction "1_1") (pintype "passive"))
      (node (ref "R23") (pin "1") (pinfunction "1_1") (pintype "passive"))
      (node (ref "R24") (pin "1") (pinfunction "1_1") (pintype "passive"))
      (node (ref "R25") (pin "1") (pinfunction "1_1") (pintype "passive"))
      (node (ref "R27") (pin "2") (pinfunction "2_2") (pintype "passive"))
      (node (ref "R28") (pin "1") (pinfunction "1_1") (pintype "passive"))
      (node (ref "R42") (pin "1") (pinfunction "1_1") (pintype "passive"))
      (node (ref "R43") (pin "1") (pinfunction "1_1") (pintype "passive"))
      (node (ref "R44") (pin "1") (pinfunction "1_1") (pintype "passive"))
      (node (ref "R45") (pin "1") (pinfunction "A_1") (pintype "passive"))
      (node (ref "R46") (pin "1") (pinfunction "A_1") (pintype "passive"))
      (node (ref "R51") (pin "1") (pinfunction "1_1") (pintype "passive"))
      (node (ref "R52") (pin "1") (pinfunction "1_1") (pintype "passive"))
      (node (ref "R53") (pin "1") (pinfunction "1_1") (pintype "passive"))
      (node (ref "R54") (pin "1") (pinfunction "1_1") (pintype "passive"))
      (node (ref "R55") (pin "1") (pinfunction "1_1") (pintype "passive"))
      (node (ref "R57") (pin "2") (pinfunction "2_2") (pintype "passive"))
      (node (ref "R58") (pin "1") (pinfunction "1_1") (pintype "passive"))
      (node (ref "R72") (pin "1") (pinfunction "A_1") (pintype "passive"))
      (node (ref "R73") (pin "1") (pinfunction "A_1") (pintype "passive"))
      (node (ref "R78") (pin "1") (pinfunction "1_1") (pintype "passive"))
      (node (ref "R79") (pin "1") (pinfunction "1_1") (pintype "passive"))
      (node (ref "R80") (pin "1") (pinfunction "1_1") (pintype "passive"))
      (node (ref "R81") (pin "1") (pinfunction "1_1") (pintype "passive"))
      (node (ref "R82") (pin "1") (pinfunction "1_1") (pintype "passive"))
      (node (ref "R84") (pin "2") (pinfunction "2_2") (pintype "passive"))
      (node (ref "R85") (pin "1") (pinfunction "1_1") (pintype "passive"))
      (node (ref "SA11") (pin "P$3") (pinfunction "2_P$3") (pintype "passive"))
      (node (ref "SA11") (pin "P$4") (pinfunction "2_P$4") (pintype "passive"))
      (node (ref "SA14") (pin "1$S") (pinfunction "S_1$S") (pintype "passive"))
      (node (ref "SA16") (pin "P$3") (pinfunction "2_P$3") (pintype "passive"))
      (node (ref "SA16") (pin "P$4") (pinfunction "2_P$4") (pintype "passive"))
      (node (ref "SA4") (pin "1$S") (pinfunction "S_1$S") (pintype "passive"))
      (node (ref "SA6") (pin "P$3") (pinfunction "2_P$3") (pintype "passive"))
      (node (ref "SA6") (pin "P$4") (pinfunction "2_P$4") (pintype "passive"))
      (node (ref "SA9") (pin "1$S") (pinfunction "S_1$S") (pintype "passive"))
      (node (ref "VT10") (pin "3") (pinfunction "E_3") (pintype "passive"))
      (node (ref "VT11") (pin "3") (pinfunction "E_3") (pintype "passive"))
      (node (ref "VT12") (pin "3") (pinfunction "E_3") (pintype "passive"))
      (node (ref "VT17") (pin "3") (pinfunction "E_3") (pintype "passive"))
      (node (ref "VT18") (pin "3") (pinfunction "E_3") (pintype "passive"))
      (node (ref "VT19") (pin "3") (pinfunction "E_3") (pintype "passive"))
      (node (ref "VT3") (pin "3") (pinfunction "E_3") (pintype "passive"))
      (node (ref "VT4") (pin "3") (pinfunction "E_3") (pintype "passive"))
      (node (ref "VT5") (pin "3") (pinfunction "E_3") (pintype "passive"))
      (node (ref "XS7") (pin "P$2") (pinfunction "2_P$2") (pintype "passive"))
    )
    (net (code "28") (name "Net-(C5-Pad1)") (class "Default")
      (node (ref "C5") (pin "1") (pinfunction "1_1") (pintype "passive"))
      (node (ref "R17") (pin "2") (pinfunction "2_2") (pintype "passive"))
      (node (ref "R87") (pin "2") (pinfunction "2_2") (pintype "passive"))
      (node (ref "SA6") (pin "P$1") (pinfunction "1_P$1") (pintype "passive"))
      (node (ref "SA6") (pin "P$2") (pinfunction "1_P$2") (pintype "passive"))
    )
    (net (code "29") (name "Net-(C9-Pad1)") (class "Default")
      (node (ref "C9") (pin "1") (pinfunction "1_1") (pintype "passive"))
      (node (ref "R47") (pin "2") (pinfunction "2_2") (pintype "passive"))
      (node (ref "R88") (pin "2") (pinfunction "2_2") (pintype "passive"))
      (node (ref "SA11") (pin "P$1") (pinfunction "1_P$1") (pintype "passive"))
      (node (ref "SA11") (pin "P$2") (pinfunction "1_P$2") (pintype "passive"))
    )
    (net (code "30") (name "Net-(C13-Pad1)") (class "Default")
      (node (ref "C13") (pin "1") (pinfunction "1_1") (pintype "passive"))
      (node (ref "R74") (pin "2") (pinfunction "2_2") (pintype "passive"))
      (node (ref "R89") (pin "2") (pinfunction "2_2") (pintype "passive"))
      (node (ref "SA16") (pin "P$1") (pinfunction "1_P$1") (pintype "passive"))
      (node (ref "SA16") (pin "P$2") (pinfunction "1_P$2") (pintype "passive"))
    )
    (net (code "31") (name "Net-(D1-ANODE)") (class "Default")
      (node (ref "D1") (pin "A") (pinfunction "ANODE_A") (pintype "passive"))
      (node (ref "R5") (pin "1") (pinfunction "1_1") (pintype "passive"))
      (node (ref "R6") (pin "1") (pinfunction "1_1") (pintype "passive"))
      (node (ref "VT3") (pin "2") (pinfunction "B_2") (pintype "passive"))
      (node (ref "VT4") (pin "1") (pinfunction "C_1") (pintype "passive"))
    )
    (net (code "32") (name "Net-(D2-ANODE)") (class "Default")
      (node (ref "D2") (pin "A") (pinfunction "ANODE_A") (pintype "passive"))
      (node (ref "D3") (pin "A") (pinfunction "ANODE_A") (pintype "passive"))
      (node (ref "R7") (pin "1") (pinfunction "1_1") (pintype "passive"))
      (node (ref "VT5") (pin "2") (pinfunction "B_2") (pintype "passive"))
    )
    (net (code "33") (name "Net-(D4-ANODE)") (class "Default")
      (node (ref "C3") (pin "+") (pinfunction "+_+") (pintype "passive"))
      (node (ref "D4") (pin "A") (pinfunction "ANODE_A") (pintype "passive"))
      (node (ref "DA2") (pin "2") (pinfunction "VO_2") (pintype "passive"))
      (node (ref "R11") (pin "2") (pinfunction "2_2") (pintype "passive"))
    )
    (net (code "34") (name "Net-(D4-CATHODE)") (class "Default")
      (node (ref "D4") (pin "C") (pinfunction "CATHODE_C") (pintype "passive"))
      (node (ref "R10") (pin "1") (pinfunction "1_1") (pintype "passive"))
      (node (ref "R10") (pin "3") (pinfunction "1_3") (pintype "passive"))
      (node (ref "VT6") (pin "3") (pinfunction "D_3") (pintype "passive"))
    )
    (net (code "35") (name "Net-(D5-ANODE)") (class "Default")
      (node (ref "C4") (pin "+") (pinfunction "+_+") (pintype "passive"))
      (node (ref "D5") (pin "A") (pinfunction "ANODE_A") (pintype "passive"))
      (node (ref "DA3") (pin "2") (pinfunction "VO_2") (pintype "passive"))
      (node (ref "R13") (pin "2") (pinfunction "2_2") (pintype "passive"))
    )
    (net (code "36") (name "Net-(D5-CATHODE)") (class "Default")
      (node (ref "D5") (pin "C") (pinfunction "CATHODE_C") (pintype "passive"))
      (node (ref "VT7") (pin "3") (pinfunction "D_3") (pintype "passive"))
      (node (ref "XS1") (pin "P$1") (pinfunction "1_P$1") (pintype "passive"))
      (node (ref "XS2") (pin "1") (pinfunction "1_1") (pintype "passive"))
    )
    (net (code "37") (name "Net-(D6-ANODE)") (class "Default")
      (node (ref "D6") (pin "A") (pinfunction "ANODE_A") (pintype "passive"))
      (node (ref "R32") (pin "1") (pinfunction "1_1") (pintype "passive"))
      (node (ref "R33") (pin "1") (pinfunction "1_1") (pintype "passive"))
      (node (ref "VT10") (pin "2") (pinfunction "B_2") (pintype "passive"))
      (node (ref "VT11") (pin "1") (pinfunction "C_1") (pintype "passive"))
    )
    (net (code "38") (name "Net-(D7-ANODE)") (class "Default")
      (node (ref "D7") (pin "A") (pinfunction "ANODE_A") (pintype "passive"))
      (node (ref "D8") (pin "A") (pinfunction "ANODE_A") (pintype "passive"))
      (node (ref "R34") (pin "1") (pinfunction "1_1") (pintype "passive"))
      (node (ref "VT12") (pin "2") (pinfunction "B_2") (pintype "passive"))
    )
    (net (code "39") (name "Net-(D9-ANODE)") (class "Default")
      (node (ref "C7") (pin "+") (pinfunction "+_+") (pintype "passive"))
      (node (ref "D9") (pin "A") (pinfunction "ANODE_A") (pintype "passive"))
      (node (ref "DA4") (pin "2") (pinfunction "VO_2") (pintype "passive"))
      (node (ref "R38") (pin "2") (pinfunction "2_2") (pintype "passive"))
    )
    (net (code "40") (name "Net-(D9-CATHODE)") (class "Default")
      (node (ref "D9") (pin "C") (pinfunction "CATHODE_C") (pintype "passive"))
      (node (ref "R37") (pin "1") (pinfunction "1_1") (pintype "passive"))
      (node (ref "R37") (pin "3") (pinfunction "1_3") (pintype "passive"))
      (node (ref "VT13") (pin "3") (pinfunction "D_3") (pintype "passive"))
    )
    (net (code "41") (name "Net-(D10-ANODE)") (class "Default")
      (node (ref "C8") (pin "+") (pinfunction "+_+") (pintype "passive"))
      (node (ref "D10") (pin "A") (pinfunction "ANODE_A") (pintype "passive"))
      (node (ref "DA5") (pin "2") (pinfunction "VO_2") (pintype "passive"))
      (node (ref "R40") (pin "2") (pinfunction "2_2") (pintype "passive"))
    )
    (net (code "42") (name "Net-(D10-CATHODE)") (class "Default")
      (node (ref "D10") (pin "C") (pinfunction "CATHODE_C") (pintype "passive"))
      (node (ref "VT14") (pin "3") (pinfunction "D_3") (pintype "passive"))
      (node (ref "XS3") (pin "P$1") (pinfunction "1_P$1") (pintype "passive"))
      (node (ref "XS4") (pin "1") (pinfunction "1_1") (pintype "passive"))
    )
    (net (code "43") (name "Net-(D11-ANODE)") (class "Default")
      (node (ref "D11") (pin "A") (pinfunction "ANODE_A") (pintype "passive"))
      (node (ref "R62") (pin "1") (pinfunction "1_1") (pintype "passive"))
      (node (ref "R63") (pin "1") (pinfunction "1_1") (pintype "passive"))
      (node (ref "VT17") (pin "2") (pinfunction "B_2") (pintype "passive"))
      (node (ref "VT18") (pin "1") (pinfunction "C_1") (pintype "passive"))
    )
    (net (code "44") (name "Net-(D12-ANODE)") (class "Default")
      (node (ref "D12") (pin "A") (pinfunction "ANODE_A") (pintype "passive"))
      (node (ref "D13") (pin "A") (pinfunction "ANODE_A") (pintype "passive"))
      (node (ref "R64") (pin "1") (pinfunction "1_1") (pintype "passive"))
      (node (ref "VT19") (pin "2") (pinfunction "B_2") (pintype "passive"))
    )
    (net (code "45") (name "Net-(D14-ANODE)") (class "Default")
      (node (ref "C11") (pin "+") (pinfunction "+_+") (pintype "passive"))
      (node (ref "D14") (pin "A") (pinfunction "ANODE_A") (pintype "passive"))
      (node (ref "DA6") (pin "2") (pinfunction "VO_2") (pintype "passive"))
      (node (ref "R68") (pin "2") (pinfunction "2_2") (pintype "passive"))
    )
    (net (code "46") (name "Net-(D14-CATHODE)") (class "Default")
      (node (ref "D14") (pin "C") (pinfunction "CATHODE_C") (pintype "passive"))
      (node (ref "R67") (pin "1") (pinfunction "1_1") (pintype "passive"))
      (node (ref "R67") (pin "3") (pinfunction "1_3") (pintype "passive"))
      (node (ref "VT20") (pin "3") (pinfunction "D_3") (pintype "passive"))
    )
    (net (code "47") (name "Net-(D15-ANODE)") (class "Default")
      (node (ref "C12") (pin "+") (pinfunction "+_+") (pintype "passive"))
      (node (ref "D15") (pin "A") (pinfunction "ANODE_A") (pintype "passive"))
      (node (ref "DA7") (pin "2") (pinfunction "VO_2") (pintype "passive"))
      (node (ref "R70") (pin "2") (pinfunction "2_2") (pintype "passive"))
    )
    (net (code "48") (name "Net-(D15-CATHODE)") (class "Default")
      (node (ref "D15") (pin "C") (pinfunction "CATHODE_C") (pintype "passive"))
      (node (ref "VT21") (pin "3") (pinfunction "D_3") (pintype "passive"))
      (node (ref "XS5") (pin "P$1") (pinfunction "1_P$1") (pintype "passive"))
      (node (ref "XS6") (pin "1") (pinfunction "1_1") (pintype "passive"))
    )
    (net (code "49") (name "Net-(DA1-ADJ)") (class "Default")
      (node (ref "DA1") (pin "1") (pinfunction "ADJ_1") (pintype "passive"))
      (node (ref "R1") (pin "1") (pinfunction "1_1") (pintype "passive"))
      (node (ref "R2") (pin "2") (pinfunction "2_2") (pintype "passive"))
    )
    (net (code "50") (name "Net-(DA2-ADJ)") (class "Default")
      (node (ref "DA2") (pin "1") (pinfunction "ADJ_1") (pintype "passive"))
      (node (ref "R15") (pin "2") (pinfunction "S_2") (pintype "passive"))
    )
    (net (code "51") (name "Net-(DA2-VI)") (class "Default")
      (node (ref "DA2") (pin "3") (pinfunction "VI_3") (pintype "input"))
      (node (ref "R12") (pin "2") (pinfunction "2_2") (pintype "passive"))
      (node (ref "R20") (pin "1") (pinfunction "1_1") (pintype "passive"))
      (node (ref "VT1") (pin "3") (pinfunction "D_3") (pintype "passive"))
    )
    (net (code "52") (name "Net-(DA3-ADJ)") (class "Default")
      (node (ref "DA3") (pin "1") (pinfunction "ADJ_1") (pintype "passive"))
      (node (ref "R16") (pin "2") (pinfunction "S_2") (pintype "passive"))
    )
    (net (code "53") (name "Net-(DA3-VI)") (class "Default")
      (node (ref "DA3") (pin "3") (pinfunction "VI_3") (pintype "input"))
      (node (ref "R14") (pin "2") (pinfunction "2_2") (pintype "passive"))
      (node (ref "R18") (pin "2") (pinfunction "2_2") (pintype "passive"))
      (node (ref "VT2") (pin "3") (pinfunction "D_3") (pintype "passive"))
    )
    (net (code "54") (name "Net-(DA4-ADJ)") (class "Default")
      (node (ref "DA4") (pin "1") (pinfunction "ADJ_1") (pintype "passive"))
      (node (ref "R45") (pin "2") (pinfunction "S_2") (pintype "passive"))
    )
    (net (code "55") (name "Net-(DA4-VI)") (class "Default")
      (node (ref "DA4") (pin "3") (pinfunction "VI_3") (pintype "input"))
      (node (ref "R39") (pin "2") (pinfunction "2_2") (pintype "passive"))
      (node (ref "R50") (pin "1") (pinfunction "1_1") (pintype "passive"))
      (node (ref "VT8") (pin "3") (pinfunction "D_3") (pintype "passive"))
    )
    (net (code "56") (name "Net-(DA5-ADJ)") (class "Default")
      (node (ref "DA5") (pin "1") (pinfunction "ADJ_1") (pintype "passive"))
      (node (ref "R46") (pin "2") (pinfunction "S_2") (pintype "passive"))
    )
    (net (code "57") (name "Net-(DA5-VI)") (class "Default")
      (node (ref "DA5") (pin "3") (pinfunction "VI_3") (pintype "input"))
      (node (ref "R41") (pin "2") (pinfunction "2_2") (pintype "passive"))
      (node (ref "R48") (pin "2") (pinfunction "2_2") (pintype "passive"))
      (node (ref "VT9") (pin "3") (pinfunction "D_3") (pintype "passive"))
    )
    (net (code "58") (name "Net-(DA6-ADJ)") (class "Default")
      (node (ref "DA6") (pin "1") (pinfunction "ADJ_1") (pintype "passive"))
      (node (ref "R72") (pin "2") (pinfunction "S_2") (pintype "passive"))
    )
    (net (code "59") (name "Net-(DA6-VI)") (class "Default")
      (node (ref "DA6") (pin "3") (pinfunction "VI_3") (pintype "input"))
      (node (ref "R69") (pin "2") (pinfunction "2_2") (pintype "passive"))
      (node (ref "R77") (pin "1") (pinfunction "1_1") (pintype "passive"))
      (node (ref "VT15") (pin "3") (pinfunction "D_3") (pintype "passive"))
    )
    (net (code "60") (name "Net-(DA7-ADJ)") (class "Default")
      (node (ref "DA7") (pin "1") (pinfunction "ADJ_1") (pintype "passive"))
      (node (ref "R73") (pin "2") (pinfunction "S_2") (pintype "passive"))
    )
    (net (code "61") (name "Net-(DA7-VI)") (class "Default")
      (node (ref "DA7") (pin "3") (pinfunction "VI_3") (pintype "input"))
      (node (ref "R71") (pin "2") (pinfunction "2_2") (pintype "passive"))
      (node (ref "R75") (pin "2") (pinfunction "2_2") (pintype "passive"))
      (node (ref "VT16") (pin "3") (pinfunction "D_3") (pintype "passive"))
    )
    (net (code "62") (name "Net-(DD1-PA8)") (class "Default")
      (node (ref "DD1") (pin "P$5") (pinfunction "PA8_P$5") (pintype "bidirectional"))
      (node (ref "JP2") (pin "3") (pinfunction "3_3") (pintype "passive"))
    )
    (net (code "63") (name "Net-(DD1-PA9)") (class "Default")
      (node (ref "DD1") (pin "P$6") (pinfunction "PA9_P$6") (pintype "bidirectional"))
      (node (ref "JP2") (pin "2") (pinfunction "2_2") (pintype "passive"))
    )
    (net (code "64") (name "Net-(DD1-PA10)") (class "Default")
      (node (ref "DD1") (pin "P$7") (pinfunction "PA10_P$7") (pintype "bidirectional"))
      (node (ref "JP2") (pin "1") (pinfunction "1_1") (pintype "passive"))
    )
    (net (code "65") (name "Net-(DD1-PB6)") (class "Default")
      (node (ref "DD1") (pin "P$14") (pinfunction "PB6_P$14") (pintype "bidirectional"))
      (node (ref "HG1") (pin "P$1") (pinfunction "CLK_P$1") (pintype "bidirectional"))
    )
    (net (code "66") (name "Net-(DD1-PB7)") (class "Default")
      (node (ref "DD1") (pin "P$15") (pinfunction "PB7_P$15") (pintype "bidirectional"))
      (node (ref "HG1") (pin "P$2") (pinfunction "DATA_P$2") (pintype "bidirectional"))
    )
    (net (code "67") (name "Net-(DD1-PB8)") (class "Default")
      (node (ref "DD1") (pin "P$16") (pinfunction "PB8_P$16") (pintype "bidirectional"))
      (node (ref "HG1") (pin "P$4") (pinfunction "CS_P$4") (pintype "bidirectional"))
    )
    (net (code "68") (name "Net-(DD1-PB9)") (class "Default")
      (node (ref "DD1") (pin "P$17") (pinfunction "PB9_P$17") (pintype "bidirectional"))
      (node (ref "HG1") (pin "P$5") (pinfunction "RESET_P$5") (pintype "bidirectional"))
    )
    (net (code "69") (name "Net-(DD1-PB15)") (class "Default")
      (node (ref "DD1") (pin "P$4") (pinfunction "PB15_P$4") (pintype "bidirectional"))
      (node (ref "JP2") (pin "4") (pinfunction "4_4") (pintype "passive"))
    )
    (net (code "70") (name "Net-(F1-Pad1)") (class "Default")
      (node (ref "F1") (pin "1") (pinfunction "1_1") (pintype "passive"))
      (node (ref "J1") (pin "1") (pinfunction "1_1") (pintype "passive"))
    )
    (net (code "71") (name "Net-(IC1A-+IN)") (class "Default")
      (node (ref "IC1") (pin "3") (pinfunction "+IN_3") (pintype "input"))
      (node (ref "R25") (pin "2") (pinfunction "2_2") (pintype "passive"))
      (node (ref "VT7") (pin "2") (pinfunction "S_2") (pintype "passive"))
    )
    (net (code "72") (name "Net-(IC1A--IN)") (class "Default")
      (node (ref "IC1") (pin "2") (pinfunction "-IN_2") (pintype "input"))
      (node (ref "R28") (pin "2") (pinfunction "2_2") (pintype "passive"))
      (node (ref "R29") (pin "1") (pinfunction "1_1") (pintype "passive"))
    )
    (net (code "73") (name "Net-(IC1B-+IN)") (class "Default")
      (node (ref "IC1") (pin "5") (pinfunction "+IN_5") (pintype "input"))
      (node (ref "R24") (pin "2") (pinfunction "2_2") (pintype "passive"))
      (node (ref "VT6") (pin "2") (pinfunction "S_2") (pintype "passive"))
    )
    (net (code "74") (name "Net-(IC1B--IN)") (class "Default")
      (node (ref "IC1") (pin "6") (pinfunction "-IN_6") (pintype "input"))
      (node (ref "R26") (pin "2") (pinfunction "2_2") (pintype "passive"))
      (node (ref "R27") (pin "1") (pinfunction "1_1") (pintype "passive"))
    )
    (net (code "75") (name "Net-(IC2A-+IN)") (class "Default")
      (node (ref "IC2") (pin "3") (pinfunction "+IN_3") (pintype "input"))
      (node (ref "R55") (pin "2") (pinfunction "2_2") (pintype "passive"))
      (node (ref "VT14") (pin "2") (pinfunction "S_2") (pintype "passive"))
    )
    (net (code "76") (name "Net-(IC2A--IN)") (class "Default")
      (node (ref "IC2") (pin "2") (pinfunction "-IN_2") (pintype "input"))
      (node (ref "R58") (pin "2") (pinfunction "2_2") (pintype "passive"))
      (node (ref "R59") (pin "1") (pinfunction "1_1") (pintype "passive"))
    )
    (net (code "77") (name "Net-(IC2B-+IN)") (class "Default")
      (node (ref "IC2") (pin "5") (pinfunction "+IN_5") (pintype "input"))
      (node (ref "R54") (pin "2") (pinfunction "2_2") (pintype "passive"))
      (node (ref "VT13") (pin "2") (pinfunction "S_2") (pintype "passive"))
    )
    (net (code "78") (name "Net-(IC2B--IN)") (class "Default")
      (node (ref "IC2") (pin "6") (pinfunction "-IN_6") (pintype "input"))
      (node (ref "R56") (pin "2") (pinfunction "2_2") (pintype "passive"))
      (node (ref "R57") (pin "1") (pinfunction "1_1") (pintype "passive"))
    )
    (net (code "79") (name "Net-(IC3A-+IN)") (class "Default")
      (node (ref "IC3") (pin "3") (pinfunction "+IN_3") (pintype "input"))
      (node (ref "R82") (pin "2") (pinfunction "2_2") (pintype "passive"))
      (node (ref "VT21") (pin "2") (pinfunction "S_2") (pintype "passive"))
    )
    (net (code "80") (name "Net-(IC3A--IN)") (class "Default")
      (node (ref "IC3") (pin "2") (pinfunction "-IN_2") (pintype "input"))
      (node (ref "R85") (pin "2") (pinfunction "2_2") (pintype "passive"))
      (node (ref "R86") (pin "1") (pinfunction "1_1") (pintype "passive"))
    )
    (net (code "81") (name "Net-(IC3B-+IN)") (class "Default")
      (node (ref "IC3") (pin "5") (pinfunction "+IN_5") (pintype "input"))
      (node (ref "R81") (pin "2") (pinfunction "2_2") (pintype "passive"))
      (node (ref "VT20") (pin "2") (pinfunction "S_2") (pintype "passive"))
    )
    (net (code "82") (name "Net-(IC3B--IN)") (class "Default")
      (node (ref "IC3") (pin "6") (pinfunction "-IN_6") (pintype "input"))
      (node (ref "R83") (pin "2") (pinfunction "2_2") (pintype "passive"))
      (node (ref "R84") (pin "1") (pinfunction "1_1") (pintype "passive"))
    )
    (net (code "83") (name "Net-(LED1-PadA)") (class "Default")
      (node (ref "LED1") (pin "A") (pinfunction "A_A") (pintype "passive"))
      (node (ref "R12") (pin "1") (pinfunction "1_1") (pintype "passive"))
    )
    (net (code "84") (name "Net-(LED2-PadA)") (class "Default")
      (node (ref "LED2") (pin "A") (pinfunction "A_A") (pintype "passive"))
      (node (ref "R14") (pin "1") (pinfunction "1_1") (pintype "passive"))
    )
    (net (code "85") (name "Net-(LED3-PadA)") (class "Default")
      (node (ref "LED3") (pin "A") (pinfunction "A_A") (pintype "passive"))
      (node (ref "R39") (pin "1") (pinfunction "1_1") (pintype "passive"))
    )
    (net (code "86") (name "Net-(LED4-PadA)") (class "Default")
      (node (ref "LED4") (pin "A") (pinfunction "A_A") (pintype "passive"))
      (node (ref "R41") (pin "1") (pinfunction "1_1") (pintype "passive"))
    )
    (net (code "87") (name "Net-(LED5-PadA)") (class "Default")
      (node (ref "LED5") (pin "A") (pinfunction "A_A") (pintype "passive"))
      (node (ref "R69") (pin "1") (pinfunction "1_1") (pintype "passive"))
    )
    (net (code "88") (name "Net-(LED6-PadA)") (class "Default")
      (node (ref "LED6") (pin "A") (pinfunction "A_A") (pintype "passive"))
      (node (ref "R71") (pin "1") (pinfunction "1_1") (pintype "passive"))
    )
    (net (code "89") (name "Net-(R10B-2)") (class "Default")
      (node (ref "R10") (pin "4") (pinfunction "2_4") (pintype "passive"))
      (node (ref "SA5") (pin "1$P") (pinfunction "P_1$P") (pintype "passive"))
    )
    (net (code "90") (name "Net-(R15-E)") (class "Default")
      (node (ref "R11") (pin "1") (pinfunction "1_1") (pintype "passive"))
      (node (ref "R15") (pin "3") (pinfunction "E_3") (pintype "passive"))
    )
    (net (code "91") (name "Net-(R16-E)") (class "Default")
      (node (ref "R13") (pin "1") (pinfunction "1_1") (pintype "passive"))
      (node (ref "R16") (pin "3") (pinfunction "E_3") (pintype "passive"))
    )
    (net (code "92") (name "Net-(R19-Pad1)") (class "Default")
      (node (ref "R19") (pin "1") (pinfunction "1_1") (pintype "passive"))
      (node (ref "R21") (pin "2") (pinfunction "2_2") (pintype "passive"))
    )
    (net (code "93") (name "Net-(R37B-2)") (class "Default")
      (node (ref "R37") (pin "4") (pinfunction "2_4") (pintype "passive"))
      (node (ref "SA10") (pin "1$P") (pinfunction "P_1$P") (pintype "passive"))
    )
    (net (code "94") (name "Net-(R45-E)") (class "Default")
      (node (ref "R38") (pin "1") (pinfunction "1_1") (pintype "passive"))
      (node (ref "R45") (pin "3") (pinfunction "E_3") (pintype "passive"))
    )
    (net (code "95") (name "Net-(R46-E)") (class "Default")
      (node (ref "R40") (pin "1") (pinfunction "1_1") (pintype "passive"))
      (node (ref "R46") (pin "3") (pinfunction "E_3") (pintype "passive"))
    )
    (net (code "96") (name "Net-(R49-Pad1)") (class "Default")
      (node (ref "R49") (pin "1") (pinfunction "1_1") (pintype "passive"))
      (node (ref "R51") (pin "2") (pinfunction "2_2") (pintype "passive"))
    )
    (net (code "97") (name "Net-(R67B-2)") (class "Default")
      (node (ref "R67") (pin "4") (pinfunction "2_4") (pintype "passive"))
      (node (ref "SA15") (pin "1$P") (pinfunction "P_1$P") (pintype "passive"))
    )
    (net (code "98") (name "Net-(R72-E)") (class "Default")
      (node (ref "R68") (pin "1") (pinfunction "1_1") (pintype "passive"))
      (node (ref "R72") (pin "3") (pinfunction "E_3") (pintype "passive"))
    )
    (net (code "99") (name "Net-(R73-E)") (class "Default")
      (node (ref "R70") (pin "1") (pinfunction "1_1") (pintype "passive"))
      (node (ref "R73") (pin "3") (pinfunction "E_3") (pintype "passive"))
    )
    (net (code "100") (name "Net-(R76-Pad1)") (class "Default")
      (node (ref "R76") (pin "1") (pinfunction "1_1") (pintype "passive"))
      (node (ref "R78") (pin "2") (pinfunction "2_2") (pintype "passive"))
    )
    (net (code "101") (name "Net-(SA1-P)") (class "Default")
      (node (ref "F1") (pin "2") (pinfunction "2_2") (pintype "passive"))
      (node (ref "SA1") (pin "3") (pinfunction "P_3") (pintype "passive"))
    )
    (net (code "102") (name "Net-(SA2-S)") (class "Default")
      (node (ref "C6") (pin "1") (pinfunction "1_1") (pintype "passive"))
      (node (ref "SA2") (pin "1$S") (pinfunction "S_1$S") (pintype "passive"))
      (node (ref "SA4") (pin "1$P") (pinfunction "P_1$P") (pintype "passive"))
    )
    (net (code "103") (name "Net-(SA3-P)") (class "Default")
      (node (ref "R10") (pin "2") (pinfunction "2_2") (pintype "passive"))
      (node (ref "SA3") (pin "1$P") (pinfunction "P_1$P") (pintype "passive"))
    )
    (net (code "104") (name "Net-(SA3-S)") (class "Default")
      (node (ref "SA3") (pin "1$S") (pinfunction "S_1$S") (pintype "passive"))
      (node (ref "SA5") (pin "1$S") (pinfunction "S_1$S") (pintype "passive"))
      (node (ref "XS1") (pin "P$2") (pinfunction "2_P$2") (pintype "passive"))
      (node (ref "XS2") (pin "2") (pinfunction "2_2") (pintype "passive"))
    )
    (net (code "105") (name "Net-(SA4-O)") (class "Default")
      (node (ref "R8") (pin "1") (pinfunction "1_1") (pintype "passive"))
      (node (ref "SA4") (pin "1$O") (pinfunction "O_1$O") (pintype "passive"))
    )
    (net (code "106") (name "Net-(SA7-S)") (class "Default")
      (node (ref "C10") (pin "1") (pinfunction "1_1") (pintype "passive"))
      (node (ref "SA7") (pin "1$S") (pinfunction "S_1$S") (pintype "passive"))
      (node (ref "SA9") (pin "1$P") (pinfunction "P_1$P") (pintype "passive"))
    )
    (net (code "107") (name "Net-(SA8-P)") (class "Default")
      (node (ref "R37") (pin "2") (pinfunction "2_2") (pintype "passive"))
      (node (ref "SA8") (pin "1$P") (pinfunction "P_1$P") (pintype "passive"))
    )
    (net (code "108") (name "Net-(SA9-O)") (class "Default")
      (node (ref "R35") (pin "1") (pinfunction "1_1") (pintype "passive"))
      (node (ref "SA9") (pin "1$O") (pinfunction "O_1$O") (pintype "passive"))
    )
    (net (code "109") (name "Net-(SA10-S)") (class "Default")
      (node (ref "SA10") (pin "1$S") (pinfunction "S_1$S") (pintype "passive"))
      (node (ref "SA8") (pin "1$S") (pinfunction "S_1$S") (pintype "passive"))
      (node (ref "XS3") (pin "P$2") (pinfunction "2_P$2") (pintype "passive"))
      (node (ref "XS4") (pin "2") (pinfunction "2_2") (pintype "passive"))
    )
    (net (code "110") (name "Net-(SA12-S)") (class "Default")
      (node (ref "C14") (pin "1") (pinfunction "1_1") (pintype "passive"))
      (node (ref "SA12") (pin "1$S") (pinfunction "S_1$S") (pintype "passive"))
      (node (ref "SA14") (pin "1$P") (pinfunction "P_1$P") (pintype "passive"))
    )
    (net (code "111") (name "Net-(SA13-P)") (class "Default")
      (node (ref "R67") (pin "2") (pinfunction "2_2") (pintype "passive"))
      (node (ref "SA13") (pin "1$P") (pinfunction "P_1$P") (pintype "passive"))
    )
    (net (code "112") (name "Net-(SA13-S)") (class "Default")
      (node (ref "SA13") (pin "1$S") (pinfunction "S_1$S") (pintype "passive"))
      (node (ref "SA15") (pin "1$S") (pinfunction "S_1$S") (pintype "passive"))
      (node (ref "XS5") (pin "P$2") (pinfunction "2_P$2") (pintype "passive"))
      (node (ref "XS6") (pin "2") (pinfunction "2_2") (pintype "passive"))
    )
    (net (code "113") (name "Net-(SA14-O)") (class "Default")
      (node (ref "R65") (pin "1") (pinfunction "1_1") (pintype "passive"))
      (node (ref "SA14") (pin "1$O") (pinfunction "O_1$O") (pintype "passive"))
    )
    (net (code "114") (name "Net-(VT1-G)") (class "Default")
      (node (ref "R3") (pin "1") (pinfunction "1_1") (pintype "passive"))
      (node (ref "VT1") (pin "1") (pinfunction "G_1") (pintype "passive"))
      (node (ref "VT3") (pin "1") (pinfunction "C_1") (pintype "passive"))
    )
    (net (code "115") (name "Net-(VT2-G)") (class "Default")
      (node (ref "R4") (pin "1") (pinfunction "1_1") (pintype "passive"))
      (node (ref "VT2") (pin "1") (pinfunction "G_1") (pintype "passive"))
      (node (ref "VT5") (pin "1") (pinfunction "C_1") (pintype "passive"))
    )
    (net (code "116") (name "Net-(VT4-B)") (class "Default")
      (node (ref "R9") (pin "1") (pinfunction "1_1") (pintype "passive"))
      (node (ref "VT4") (pin "2") (pinfunction "B_2") (pintype "passive"))
    )
    (net (code "117") (name "Net-(VT6-G)") (class "Default")
      (node (ref "R18") (pin "1") (pinfunction "1_1") (pintype "passive"))
      (node (ref "R22") (pin "2") (pinfunction "2_2") (pintype "passive"))
      (node (ref "VT6") (pin "1") (pinfunction "G_1") (pintype "passive"))
    )
    (net (code "118") (name "Net-(VT7-G)") (class "Default")
      (node (ref "R20") (pin "2") (pinfunction "2_2") (pintype "passive"))
      (node (ref "R23") (pin "2") (pinfunction "2_2") (pintype "passive"))
      (node (ref "VT7") (pin "1") (pinfunction "G_1") (pintype "passive"))
    )
    (net (code "119") (name "Net-(VT10-C)") (class "Default")
      (node (ref "R30") (pin "1") (pinfunction "1_1") (pintype "passive"))
      (node (ref "VT10") (pin "1") (pinfunction "C_1") (pintype "passive"))
      (node (ref "VT8") (pin "1") (pinfunction "G_1") (pintype "passive"))
    )
    (net (code "120") (name "Net-(VT11-B)") (class "Default")
      (node (ref "R36") (pin "1") (pinfunction "1_1") (pintype "passive"))
      (node (ref "VT11") (pin "2") (pinfunction "B_2") (pintype "passive"))
    )
    (net (code "121") (name "Net-(VT12-C)") (class "Default")
      (node (ref "R31") (pin "1") (pinfunction "1_1") (pintype "passive"))
      (node (ref "VT12") (pin "1") (pinfunction "C_1") (pintype "passive"))
      (node (ref "VT9") (pin "1") (pinfunction "G_1") (pintype "passive"))
    )
    (net (code "122") (name "Net-(VT13-G)") (class "Default")
      (node (ref "R48") (pin "1") (pinfunction "1_1") (pintype "passive"))
      (node (ref "R52") (pin "2") (pinfunction "2_2") (pintype "passive"))
      (node (ref "VT13") (pin "1") (pinfunction "G_1") (pintype "passive"))
    )
    (net (code "123") (name "Net-(VT14-G)") (class "Default")
      (node (ref "R50") (pin "2") (pinfunction "2_2") (pintype "passive"))
      (node (ref "R53") (pin "2") (pinfunction "2_2") (pintype "passive"))
      (node (ref "VT14") (pin "1") (pinfunction "G_1") (pintype "passive"))
    )
    (net (code "124") (name "Net-(VT15-G)") (class "Default")
      (node (ref "R60") (pin "1") (pinfunction "1_1") (pintype "passive"))
      (node (ref "VT15") (pin "1") (pinfunction "G_1") (pintype "passive"))
      (node (ref "VT17") (pin "1") (pinfunction "C_1") (pintype "passive"))
    )
    (net (code "125") (name "Net-(VT16-G)") (class "Default")
      (node (ref "R61") (pin "1") (pinfunction "1_1") (pintype "passive"))
      (node (ref "VT16") (pin "1") (pinfunction "G_1") (pintype "passive"))
      (node (ref "VT19") (pin "1") (pinfunction "C_1") (pintype "passive"))
    )
    (net (code "126") (name "Net-(VT18-B)") (class "Default")
      (node (ref "R66") (pin "1") (pinfunction "1_1") (pintype "passive"))
      (node (ref "VT18") (pin "2") (pinfunction "B_2") (pintype "passive"))
    )
    (net (code "127") (name "Net-(VT20-G)") (class "Default")
      (node (ref "R75") (pin "1") (pinfunction "1_1") (pintype "passive"))
      (node (ref "R79") (pin "2") (pinfunction "2_2") (pintype "passive"))
      (node (ref "VT20") (pin "1") (pinfunction "G_1") (pintype "passive"))
    )
    (net (code "128") (name "Net-(VT21-G)") (class "Default")
      (node (ref "R77") (pin "2") (pinfunction "2_2") (pintype "passive"))
      (node (ref "R80") (pin "2") (pinfunction "2_2") (pintype "passive"))
      (node (ref "VT21") (pin "1") (pinfunction "G_1") (pintype "passive"))
    )
    (net (code "129") (name "VCC") (class "Default")
      (node (ref "C2") (pin "+") (pinfunction "+_+") (pintype "passive"))
      (node (ref "DA1") (pin "2") (pinfunction "VO_2") (pintype "passive"))
      (node (ref "DD1") (pin "P$20") (pinfunction "3.3V1_P$20") (pintype "bidirectional"))
      (node (ref "DD1") (pin "P$23") (pinfunction "3.3V_P$23") (pintype "bidirectional"))
      (node (ref "HG1") (pin "P$10") (pinfunction "VCC_P$10") (pintype "bidirectional"))
      (node (ref "HG1") (pin "P$6") (pinfunction "LED+_P$6") (pintype "bidirectional"))
      (node (ref "HG1") (pin "P$9") (pinfunction "VCC_P$9") (pintype "bidirectional"))
      (node (ref "R1") (pin "2") (pinfunction "2_2") (pintype "passive"))
      (node (ref "R17") (pin "1") (pinfunction "1_1") (pintype "passive"))
      (node (ref "R19") (pin "3") (pinfunction "2_3") (pintype "passive"))
      (node (ref "R32") (pin "2") (pinfunction "2_2") (pintype "passive"))
      (node (ref "R33") (pin "2") (pinfunction "2_2") (pintype "passive"))
      (node (ref "R34") (pin "2") (pinfunction "2_2") (pintype "passive"))
      (node (ref "R35") (pin "2") (pinfunction "2_2") (pintype "passive"))
      (node (ref "R47") (pin "1") (pinfunction "1_1") (pintype "passive"))
      (node (ref "R49") (pin "3") (pinfunction "2_3") (pintype "passive"))
      (node (ref "R5") (pin "2") (pinfunction "2_2") (pintype "passive"))
      (node (ref "R6") (pin "2") (pinfunction "2_2") (pintype "passive"))
      (node (ref "R62") (pin "2") (pinfunction "2_2") (pintype "passive"))
      (node (ref "R63") (pin "2") (pinfunction "2_2") (pintype "passive"))
      (node (ref "R64") (pin "2") (pinfunction "2_2") (pintype "passive"))
      (node (ref "R65") (pin "2") (pinfunction "2_2") (pintype "passive"))
      (node (ref "R7") (pin "2") (pinfunction "2_2") (pintype "passive"))
      (node (ref "R74") (pin "1") (pinfunction "1_1") (pintype "passive"))
      (node (ref "R76") (pin "3") (pinfunction "2_3") (pintype "passive"))
      (node (ref "R8") (pin "2") (pinfunction "2_2") (pintype "passive"))
      (node (ref "S1") (pin "4") (pinfunction "4_4") (pintype "passive"))
      (node (ref "S1") (pin "5") (pinfunction "5_5") (pintype "passive"))
      (node (ref "S1") (pin "6") (pinfunction "6_6") (pintype "passive"))
    )
    (net (code "130") (name "unconnected-(DD1-5V-PadP$18)") (class "Default")
      (node (ref "DD1") (pin "P$18") (pinfunction "5V_P$18") (pintype "bidirectional"))
    )
    (net (code "131") (name "unconnected-(DD1-PC13-PadP$39)") (class "Default")
      (node (ref "DD1") (pin "P$39") (pinfunction "PC13_P$39") (pintype "bidirectional"))
    )
    (net (code "132") (name "unconnected-(DD1-PC14-PadP$38)") (class "Default")
      (node (ref "DD1") (pin "P$38") (pinfunction "PC14_P$38") (pintype "bidirectional"))
    )
    (net (code "133") (name "unconnected-(DD1-PC15-PadP$37)") (class "Default")
      (node (ref "DD1") (pin "P$37") (pinfunction "PC15_P$37") (pintype "bidirectional"))
    )
    (net (code "134") (name "unconnected-(DD1-RESET-PadP$24)") (class "Default")
      (node (ref "DD1") (pin "P$24") (pinfunction "RESET_P$24") (pintype "bidirectional"))
    )
    (net (code "135") (name "unconnected-(DD1-VBAT-PadP$40)") (class "Default")
      (node (ref "DD1") (pin "P$40") (pinfunction "VBAT_P$40") (pintype "bidirectional"))
    )
    (net (code "136") (name "unconnected-(HG1-N{slash}A-PadP$8)") (class "Default")
      (node (ref "HG1") (pin "P$8") (pinfunction "N/A_P$8") (pintype "bidirectional"))
    )
    (net (code "137") (name "unconnected-(J1-Pad2)") (class "Default")
      (node (ref "J1") (pin "2") (pinfunction "2_2") (pintype "passive"))
    )
    (net (code "138") (name "unconnected-(SA1-S-Pad2)") (class "Default")
      (node (ref "SA1") (pin "2") (pinfunction "S_2") (pintype "passive"))
    )
    (net (code "139") (name "unconnected-(SA3-O-Pad1$O)") (class "Default")
      (node (ref "SA3") (pin "1$O") (pinfunction "O_1$O") (pintype "passive"))
    )
    (net (code "140") (name "unconnected-(SA5-O-Pad1$O)") (class "Default")
      (node (ref "SA5") (pin "1$O") (pinfunction "O_1$O") (pintype "passive"))
    )
    (net (code "141") (name "unconnected-(SA8-O-Pad1$O)") (class "Default")
      (node (ref "SA8") (pin "1$O") (pinfunction "O_1$O") (pintype "passive"))
    )
    (net (code "142") (name "unconnected-(SA10-O-Pad1$O)") (class "Default")
      (node (ref "SA10") (pin "1$O") (pinfunction "O_1$O") (pintype "passive"))
    )
    (net (code "143") (name "unconnected-(SA13-O-Pad1$O)") (class "Default")
      (node (ref "SA13") (pin "1$O") (pinfunction "O_1$O") (pintype "passive"))
    )
    (net (code "144") (name "unconnected-(SA15-O-Pad1$O)") (class "Default")
      (node (ref "SA15") (pin "1$O") (pinfunction "O_1$O") (pintype "passive"))
    )
  )
)
